# sr61-revC.net
KiCad netlist of a schematic drawn in EAGLE
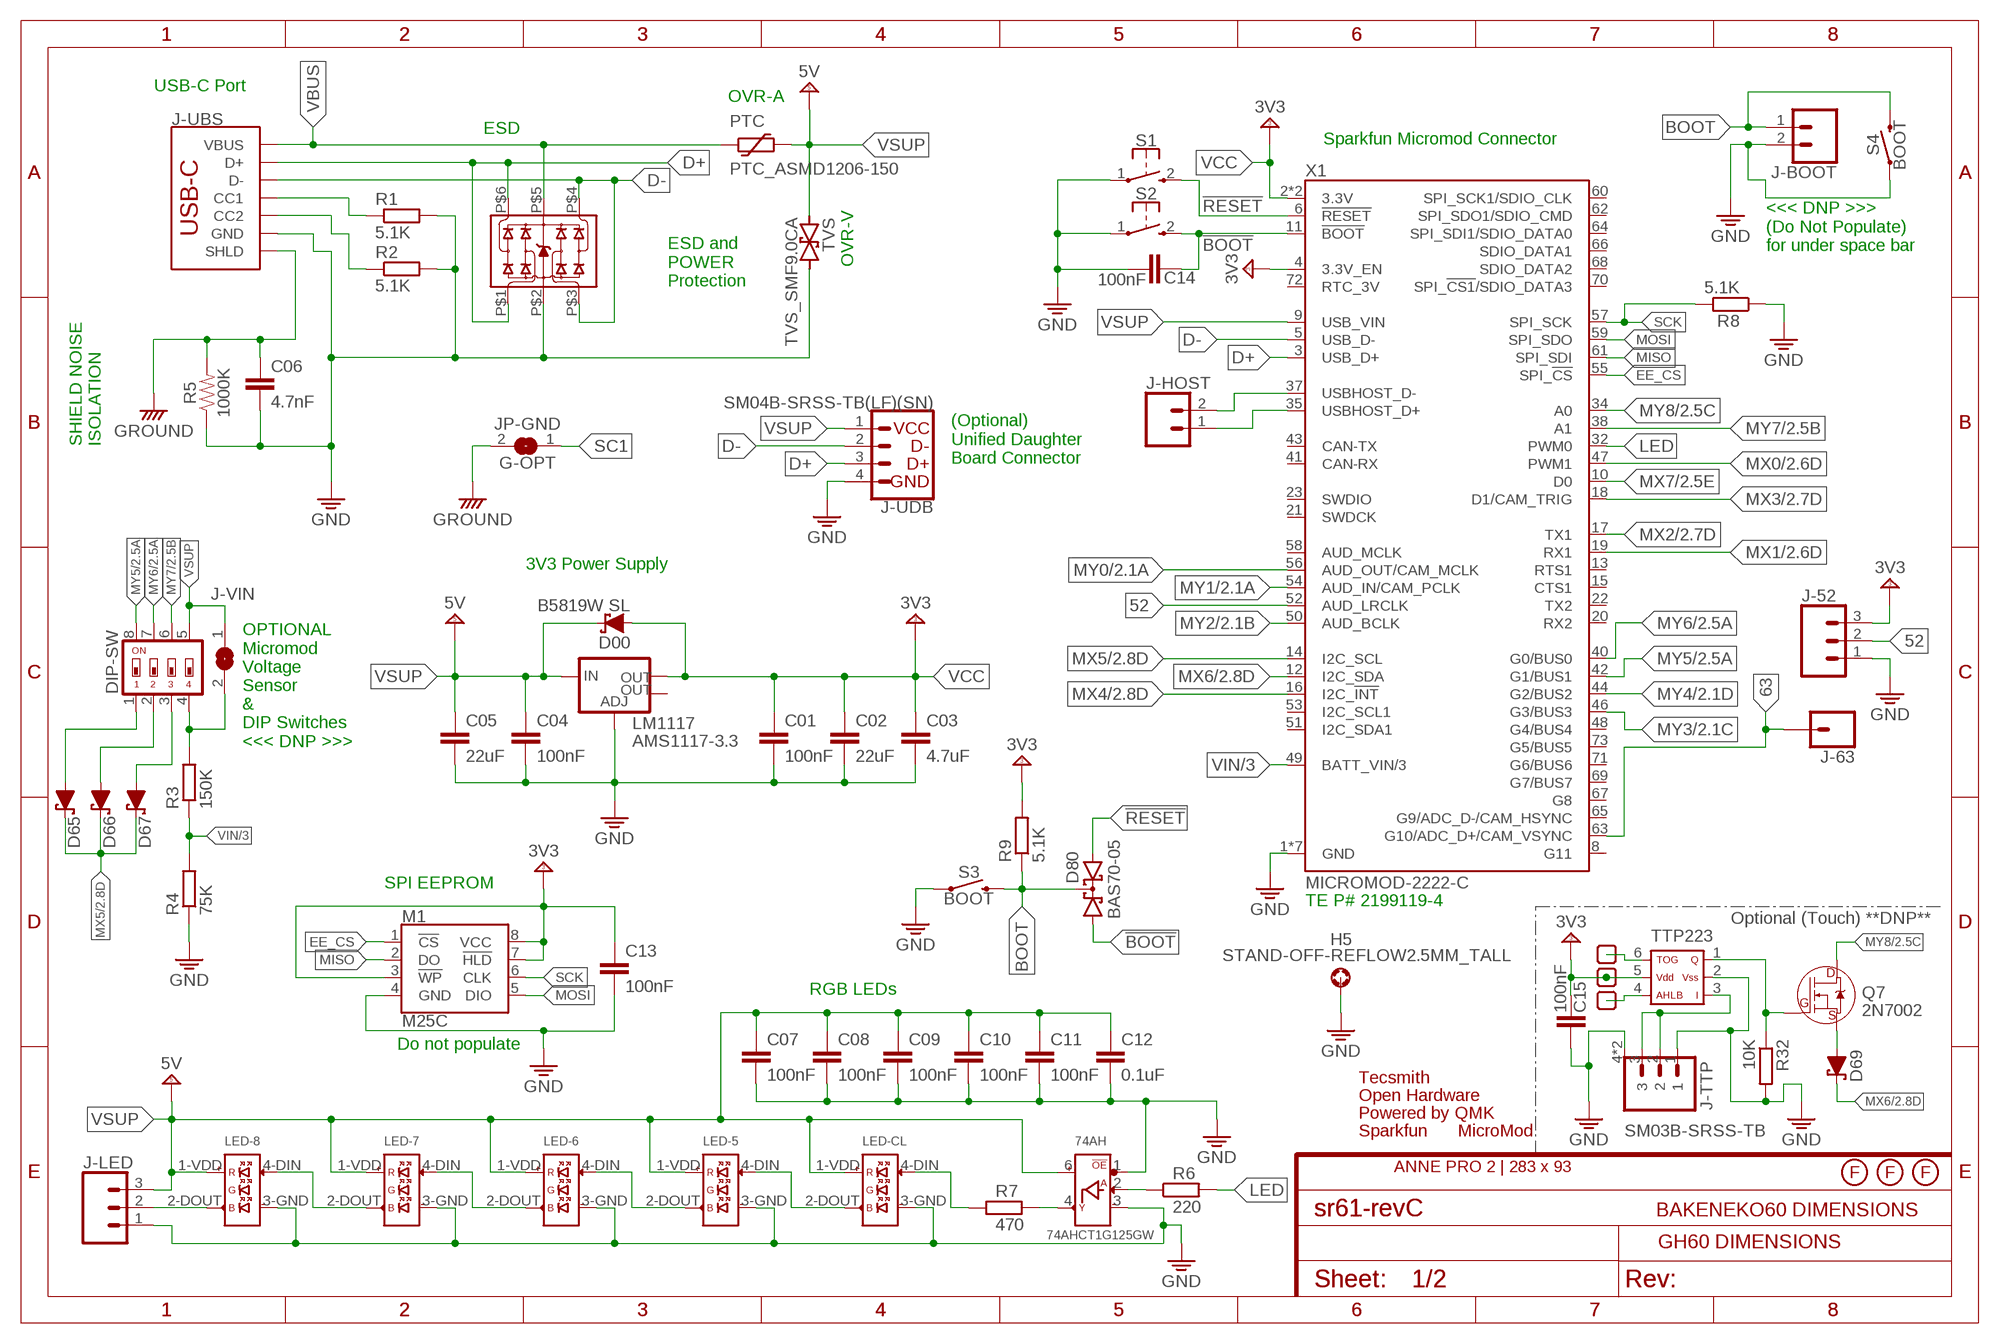
[diagram p0: schematic, sheet 1]
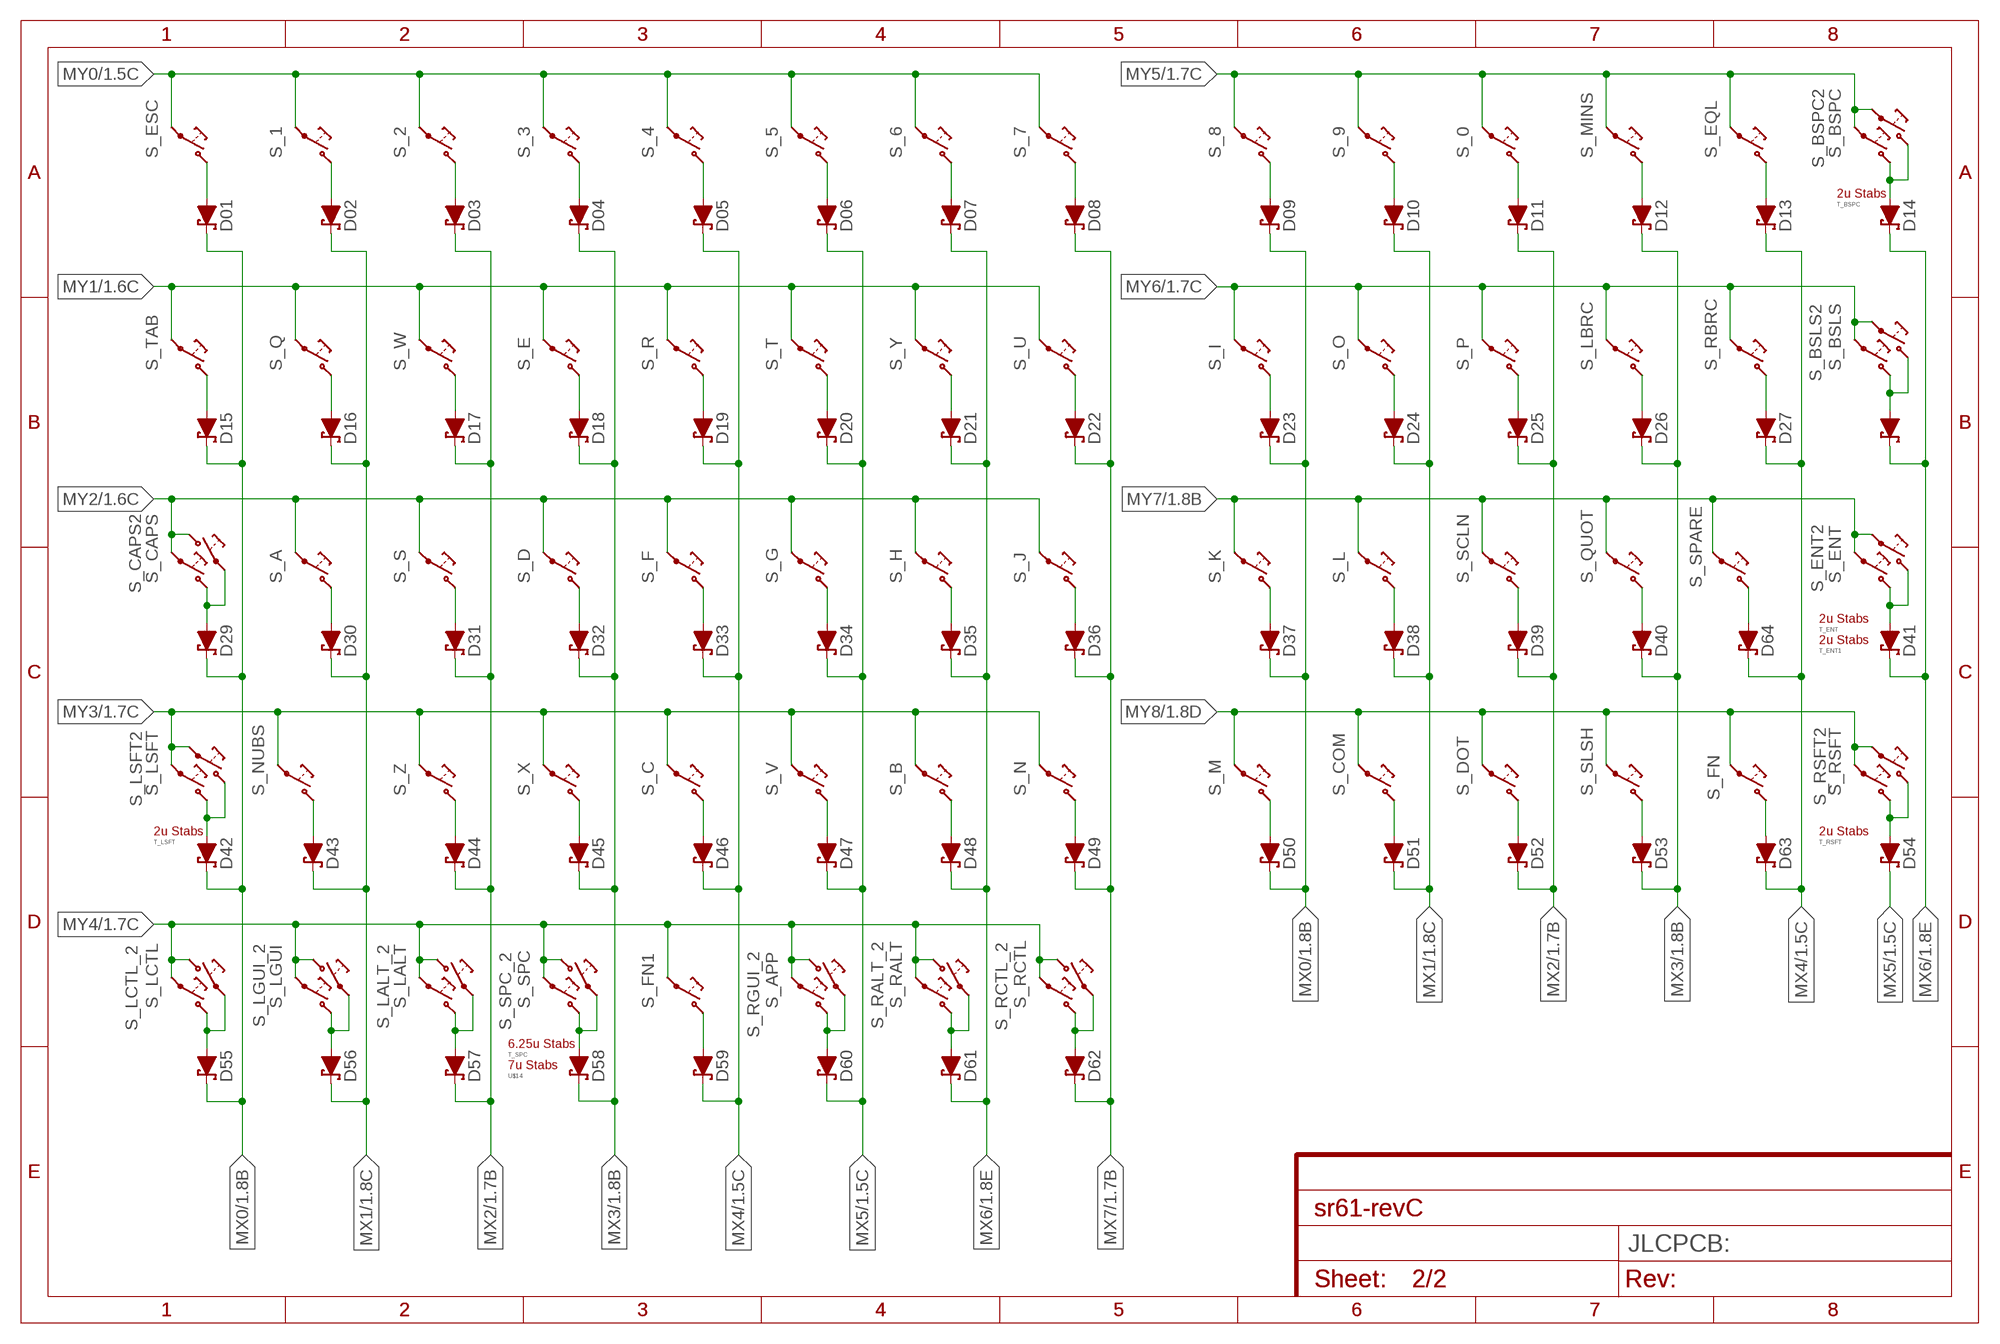
[diagram p1: schematic, sheet 2]

(export (version "E")
  (design (tool "Eeschema 10.0.6"))
  (components
    (comp (ref "D01")
      (value "1N5819WS")
      (footprint "eagle-import:SOD-123")
      (libsource (lib "eagle-import") (part "1N5819WS"))
    )
    (comp (ref "D02")
      (value "1N5819WS")
      (footprint "eagle-import:SOD-123")
      (libsource (lib "eagle-import") (part "1N5819WS"))
    )
    (comp (ref "D03")
      (value "1N5819WS")
      (footprint "eagle-import:SOD-123")
      (libsource (lib "eagle-import") (part "1N5819WS"))
    )
    (comp (ref "D04")
      (value "1N5819WS")
      (footprint "eagle-import:SOD-123")
      (libsource (lib "eagle-import") (part "1N5819WS"))
    )
    (comp (ref "D05")
      (value "1N5819WS")
      (footprint "eagle-import:SOD-123")
      (libsource (lib "eagle-import") (part "1N5819WS"))
    )
    (comp (ref "D06")
      (value "1N5819WS")
      (footprint "eagle-import:SOD-123")
      (libsource (lib "eagle-import") (part "1N5819WS"))
    )
    (comp (ref "D07")
      (value "1N5819WS")
      (footprint "eagle-import:SOD-123")
      (libsource (lib "eagle-import") (part "1N5819WS"))
    )
    (comp (ref "D08")
      (value "1N5819WS")
      (footprint "eagle-import:SOD-123")
      (libsource (lib "eagle-import") (part "1N5819WS"))
    )
    (comp (ref "D09")
      (value "1N5819WS")
      (footprint "eagle-import:SOD-123")
      (libsource (lib "eagle-import") (part "1N5819WS"))
    )
    (comp (ref "D10")
      (value "1N5819WS")
      (footprint "eagle-import:SOD-123")
      (libsource (lib "eagle-import") (part "1N5819WS"))
    )
    (comp (ref "D11")
      (value "1N5819WS")
      (footprint "eagle-import:SOD-123")
      (libsource (lib "eagle-import") (part "1N5819WS"))
    )
    (comp (ref "D12")
      (value "1N5819WS")
      (footprint "eagle-import:SOD-123")
      (libsource (lib "eagle-import") (part "1N5819WS"))
    )
    (comp (ref "D13")
      (value "1N5819WS")
      (footprint "eagle-import:SOD-123")
      (libsource (lib "eagle-import") (part "1N5819WS"))
    )
    (comp (ref "D14")
      (value "1N5819WS")
      (footprint "eagle-import:SOD-123")
      (libsource (lib "eagle-import") (part "1N5819WS"))
    )
    (comp (ref "D15")
      (value "1N5819WS")
      (footprint "eagle-import:SOD-123")
      (libsource (lib "eagle-import") (part "1N5819WS"))
    )
    (comp (ref "D16")
      (value "1N5819WS")
      (footprint "eagle-import:SOD-123")
      (libsource (lib "eagle-import") (part "1N5819WS"))
    )
    (comp (ref "D17")
      (value "1N5819WS")
      (footprint "eagle-import:SOD-123")
      (libsource (lib "eagle-import") (part "1N5819WS"))
    )
    (comp (ref "D18")
      (value "1N5819WS")
      (footprint "eagle-import:SOD-123")
      (libsource (lib "eagle-import") (part "1N5819WS"))
    )
    (comp (ref "D19")
      (value "1N5819WS")
      (footprint "eagle-import:SOD-123")
      (libsource (lib "eagle-import") (part "1N5819WS"))
    )
    (comp (ref "D20")
      (value "1N5819WS")
      (footprint "eagle-import:SOD-123")
      (libsource (lib "eagle-import") (part "1N5819WS"))
    )
    (comp (ref "D21")
      (value "1N5819WS")
      (footprint "eagle-import:SOD-123")
      (libsource (lib "eagle-import") (part "1N5819WS"))
    )
    (comp (ref "D22")
      (value "1N5819WS")
      (footprint "eagle-import:SOD-123")
      (libsource (lib "eagle-import") (part "1N5819WS"))
    )
    (comp (ref "D23")
      (value "1N5819WS")
      (footprint "eagle-import:SOD-123")
      (libsource (lib "eagle-import") (part "1N5819WS"))
    )
    (comp (ref "D24")
      (value "1N5819WS")
      (footprint "eagle-import:SOD-123")
      (libsource (lib "eagle-import") (part "1N5819WS"))
    )
    (comp (ref "D25")
      (value "1N5819WS")
      (footprint "eagle-import:SOD-123")
      (libsource (lib "eagle-import") (part "1N5819WS"))
    )
    (comp (ref "D26")
      (value "1N5819WS")
      (footprint "eagle-import:SOD-123")
      (libsource (lib "eagle-import") (part "1N5819WS"))
    )
    (comp (ref "D27")
      (value "1N5819WS")
      (footprint "eagle-import:SOD-123")
      (libsource (lib "eagle-import") (part "1N5819WS"))
    )
    (comp (ref "D28")
      (value "1N5819WS")
      (footprint "eagle-import:SOD-123")
      (libsource (lib "eagle-import") (part "1N5819WS"))
    )
    (comp (ref "D29")
      (value "1N5819WS")
      (footprint "eagle-import:SOD-123")
      (libsource (lib "eagle-import") (part "1N5819WS"))
    )
    (comp (ref "D30")
      (value "1N5819WS")
      (footprint "eagle-import:SOD-123")
      (libsource (lib "eagle-import") (part "1N5819WS"))
    )
    (comp (ref "D31")
      (value "1N5819WS")
      (footprint "eagle-import:SOD-123")
      (libsource (lib "eagle-import") (part "1N5819WS"))
    )
    (comp (ref "D32")
      (value "1N5819WS")
      (footprint "eagle-import:SOD-123")
      (libsource (lib "eagle-import") (part "1N5819WS"))
    )
    (comp (ref "D33")
      (value "1N5819WS")
      (footprint "eagle-import:SOD-123")
      (libsource (lib "eagle-import") (part "1N5819WS"))
    )
    (comp (ref "D34")
      (value "1N5819WS")
      (footprint "eagle-import:SOD-123")
      (libsource (lib "eagle-import") (part "1N5819WS"))
    )
    (comp (ref "D35")
      (value "1N5819WS")
      (footprint "eagle-import:SOD-123")
      (libsource (lib "eagle-import") (part "1N5819WS"))
    )
    (comp (ref "D36")
      (value "1N5819WS")
      (footprint "eagle-import:SOD-123")
      (libsource (lib "eagle-import") (part "1N5819WS"))
    )
    (comp (ref "D37")
      (value "1N5819WS")
      (footprint "eagle-import:SOD-123")
      (libsource (lib "eagle-import") (part "1N5819WS"))
    )
    (comp (ref "D38")
      (value "1N5819WS")
      (footprint "eagle-import:SOD-123")
      (libsource (lib "eagle-import") (part "1N5819WS"))
    )
    (comp (ref "D39")
      (value "1N5819WS")
      (footprint "eagle-import:SOD-123")
      (libsource (lib "eagle-import") (part "1N5819WS"))
    )
    (comp (ref "D40")
      (value "1N5819WS")
      (footprint "eagle-import:SOD-123")
      (libsource (lib "eagle-import") (part "1N5819WS"))
    )
    (comp (ref "D41")
      (value "1N5819WS")
      (footprint "eagle-import:SOD-123")
      (libsource (lib "eagle-import") (part "1N5819WS"))
    )
    (comp (ref "D42")
      (value "1N5819WS")
      (footprint "eagle-import:SOD-123")
      (libsource (lib "eagle-import") (part "1N5819WS"))
    )
    (comp (ref "D43")
      (value "1N5819WS")
      (footprint "eagle-import:SOD-123")
      (libsource (lib "eagle-import") (part "1N5819WS"))
    )
    (comp (ref "D44")
      (value "1N5819WS")
      (footprint "eagle-import:SOD-123")
      (libsource (lib "eagle-import") (part "1N5819WS"))
    )
    (comp (ref "D45")
      (value "1N5819WS")
      (footprint "eagle-import:SOD-123")
      (libsource (lib "eagle-import") (part "1N5819WS"))
    )
    (comp (ref "D46")
      (value "1N5819WS")
      (footprint "eagle-import:SOD-123")
      (libsource (lib "eagle-import") (part "1N5819WS"))
    )
    (comp (ref "D47")
      (value "1N5819WS")
      (footprint "eagle-import:SOD-123")
      (libsource (lib "eagle-import") (part "1N5819WS"))
    )
    (comp (ref "D48")
      (value "1N5819WS")
      (footprint "eagle-import:SOD-123")
      (libsource (lib "eagle-import") (part "1N5819WS"))
    )
    (comp (ref "D49")
      (value "1N5819WS")
      (footprint "eagle-import:SOD-123")
      (libsource (lib "eagle-import") (part "1N5819WS"))
    )
    (comp (ref "D50")
      (value "1N5819WS")
      (footprint "eagle-import:SOD-123")
      (libsource (lib "eagle-import") (part "1N5819WS"))
    )
    (comp (ref "D51")
      (value "1N5819WS")
      (footprint "eagle-import:SOD-123")
      (libsource (lib "eagle-import") (part "1N5819WS"))
    )
    (comp (ref "D52")
      (value "1N5819WS")
      (footprint "eagle-import:SOD-123")
      (libsource (lib "eagle-import") (part "1N5819WS"))
    )
    (comp (ref "D53")
      (value "1N5819WS")
      (footprint "eagle-import:SOD-123")
      (libsource (lib "eagle-import") (part "1N5819WS"))
    )
    (comp (ref "D54")
      (value "1N5819WS")
      (footprint "eagle-import:SOD-123")
      (libsource (lib "eagle-import") (part "1N5819WS"))
    )
    (comp (ref "D55")
      (value "1N5819WS")
      (footprint "eagle-import:SOD-123")
      (libsource (lib "eagle-import") (part "1N5819WS"))
    )
    (comp (ref "D56")
      (value "1N5819WS")
      (footprint "eagle-import:SOD-123")
      (libsource (lib "eagle-import") (part "1N5819WS"))
    )
    (comp (ref "D57")
      (value "1N5819WS")
      (footprint "eagle-import:SOD-123")
      (libsource (lib "eagle-import") (part "1N5819WS"))
    )
    (comp (ref "D58")
      (value "1N5819WS")
      (footprint "eagle-import:SOD-123")
      (libsource (lib "eagle-import") (part "1N5819WS"))
    )
    (comp (ref "D59")
      (value "1N5819WS")
      (footprint "eagle-import:SOD-123")
      (libsource (lib "eagle-import") (part "1N5819WS"))
    )
    (comp (ref "D60")
      (value "1N5819WS")
      (footprint "eagle-import:SOD-123")
      (libsource (lib "eagle-import") (part "1N5819WS"))
    )
    (comp (ref "D61")
      (value "1N5819WS")
      (footprint "eagle-import:SOD-123")
      (libsource (lib "eagle-import") (part "1N5819WS"))
    )
    (comp (ref "D62")
      (value "1N5819WS")
      (footprint "eagle-import:SOD-123")
      (libsource (lib "eagle-import") (part "1N5819WS"))
    )
    (comp (ref "D63")
      (value "1N5819WS")
      (footprint "eagle-import:SOD-123")
      (libsource (lib "eagle-import") (part "1N5819WS"))
    )
    (comp (ref "D64")
      (value "1N5819WS")
      (footprint "eagle-import:SOD-123")
      (libsource (lib "eagle-import") (part "1N5819WS"))
    )
    (comp (ref "S_0")
      (value "MX-5-PIN-HOTSWAP-VIA")
      (footprint "eagle-import:MX-5-PIN-HOTSWAP-VIA")
      (libsource (lib "eagle-import") (part "MX-5-PIN-HOTSWAP-VIA"))
    )
    (comp (ref "S_1")
      (value "MX-5-PIN-HOTSWAP-VIA")
      (footprint "eagle-import:MX-5-PIN-HOTSWAP-VIA")
      (libsource (lib "eagle-import") (part "MX-5-PIN-HOTSWAP-VIA"))
    )
    (comp (ref "S_2")
      (value "MX-5-PIN-HOTSWAP-VIA")
      (footprint "eagle-import:MX-5-PIN-HOTSWAP-VIA")
      (libsource (lib "eagle-import") (part "MX-5-PIN-HOTSWAP-VIA"))
    )
    (comp (ref "S_3")
      (value "MX-5-PIN-HOTSWAP-VIA")
      (footprint "eagle-import:MX-5-PIN-HOTSWAP-VIA")
      (libsource (lib "eagle-import") (part "MX-5-PIN-HOTSWAP-VIA"))
    )
    (comp (ref "S_4")
      (value "MX-5-PIN-HOTSWAP-VIA")
      (footprint "eagle-import:MX-5-PIN-HOTSWAP-VIA")
      (libsource (lib "eagle-import") (part "MX-5-PIN-HOTSWAP-VIA"))
    )
    (comp (ref "S_5")
      (value "MX-5-PIN-HOTSWAP-VIA")
      (footprint "eagle-import:MX-5-PIN-HOTSWAP-VIA")
      (libsource (lib "eagle-import") (part "MX-5-PIN-HOTSWAP-VIA"))
    )
    (comp (ref "S_6")
      (value "MX-5-PIN-HOTSWAP-VIA")
      (footprint "eagle-import:MX-5-PIN-HOTSWAP-VIA")
      (libsource (lib "eagle-import") (part "MX-5-PIN-HOTSWAP-VIA"))
    )
    (comp (ref "S_7")
      (value "MX-5-PIN-HOTSWAP-VIA")
      (footprint "eagle-import:MX-5-PIN-HOTSWAP-VIA")
      (libsource (lib "eagle-import") (part "MX-5-PIN-HOTSWAP-VIA"))
    )
    (comp (ref "S_8")
      (value "MX-5-PIN-HOTSWAP-VIA")
      (footprint "eagle-import:MX-5-PIN-HOTSWAP-VIA")
      (libsource (lib "eagle-import") (part "MX-5-PIN-HOTSWAP-VIA"))
    )
    (comp (ref "S_9")
      (value "MX-5-PIN-HOTSWAP-VIA")
      (footprint "eagle-import:MX-5-PIN-HOTSWAP-VIA")
      (libsource (lib "eagle-import") (part "MX-5-PIN-HOTSWAP-VIA"))
    )
    (comp (ref "S_A")
      (value "MX-5-PIN-HOTSWAP-VIA")
      (footprint "eagle-import:MX-5-PIN-HOTSWAP-VIA")
      (libsource (lib "eagle-import") (part "MX-5-PIN-HOTSWAP-VIA"))
    )
    (comp (ref "S_APP")
      (value "MX-5-PIN-HOTSWAP-VIA")
      (footprint "eagle-import:MX-5-PIN-HOTSWAP-VIA")
      (libsource (lib "eagle-import") (part "MX-5-PIN-HOTSWAP-VIA"))
    )
    (comp (ref "S_B")
      (value "MX-5-PIN-HOTSWAP-VIA")
      (footprint "eagle-import:MX-5-PIN-HOTSWAP-VIA")
      (libsource (lib "eagle-import") (part "MX-5-PIN-HOTSWAP-VIA"))
    )
    (comp (ref "S_BSLS")
      (value "MX-5-PIN-HOTSWAP-VIA")
      (footprint "eagle-import:MX-5-PIN-HOTSWAP-VIA")
      (libsource (lib "eagle-import") (part "MX-5-PIN-HOTSWAP-VIA"))
    )
    (comp (ref "S_BSLS2")
      (value "MX-5-PIN-HOTSWAP-VIANO-SILK")
      (footprint "eagle-import:MX-5-PIN-HOTSWAP-VIA-NS")
      (libsource (lib "eagle-import") (part "MX-5-PIN-HOTSWAP-VIANO-SILK"))
    )
    (comp (ref "S_BSPC")
      (value "MX-5-PIN-HOTSWAP-VIA")
      (footprint "eagle-import:MX-5-PIN-HOTSWAP-VIA")
      (libsource (lib "eagle-import") (part "MX-5-PIN-HOTSWAP-VIA"))
    )
    (comp (ref "S_BSPC2")
      (value "MX-5-PIN-HOTSWAP-VIANO-SILK")
      (footprint "eagle-import:MX-5-PIN-HOTSWAP-VIA-NS")
      (libsource (lib "eagle-import") (part "MX-5-PIN-HOTSWAP-VIANO-SILK"))
    )
    (comp (ref "S_C")
      (value "MX-5-PIN-HOTSWAP-VIA")
      (footprint "eagle-import:MX-5-PIN-HOTSWAP-VIA")
      (libsource (lib "eagle-import") (part "MX-5-PIN-HOTSWAP-VIA"))
    )
    (comp (ref "S_CAPS")
      (value "MX-5-PIN-HOTSWAP-VIA")
      (footprint "eagle-import:MX-5-PIN-HOTSWAP-VIA")
      (libsource (lib "eagle-import") (part "MX-5-PIN-HOTSWAP-VIA"))
    )
    (comp (ref "S_CAPS2")
      (value "MX-5-PIN-MILMAX-3305-XNO-SILK")
      (footprint "eagle-import:MX-5-PIN-MILMAX-3305-X-NS")
      (libsource (lib "eagle-import") (part "MX-5-PIN-MILMAX-3305-XNO-SILK"))
    )
    (comp (ref "S_COM")
      (value "MX-5-PIN-HOTSWAP-VIA")
      (footprint "eagle-import:MX-5-PIN-HOTSWAP-VIA")
      (libsource (lib "eagle-import") (part "MX-5-PIN-HOTSWAP-VIA"))
    )
    (comp (ref "S_D")
      (value "MX-5-PIN-HOTSWAP-VIA")
      (footprint "eagle-import:MX-5-PIN-HOTSWAP-VIA")
      (libsource (lib "eagle-import") (part "MX-5-PIN-HOTSWAP-VIA"))
    )
    (comp (ref "S_DOT")
      (value "MX-5-PIN-HOTSWAP-VIA")
      (footprint "eagle-import:MX-5-PIN-HOTSWAP-VIA")
      (libsource (lib "eagle-import") (part "MX-5-PIN-HOTSWAP-VIA"))
    )
    (comp (ref "S_E")
      (value "MX-5-PIN-HOTSWAP-VIA")
      (footprint "eagle-import:MX-5-PIN-HOTSWAP-VIA")
      (libsource (lib "eagle-import") (part "MX-5-PIN-HOTSWAP-VIA"))
    )
    (comp (ref "S_ENT")
      (value "MX-5-PIN-HOTSWAP-VIA")
      (footprint "eagle-import:MX-5-PIN-HOTSWAP-VIA")
      (libsource (lib "eagle-import") (part "MX-5-PIN-HOTSWAP-VIA"))
    )
    (comp (ref "S_ENT2")
      (value "MX-5-PIN-HOTSWAP-VIANO-SILK")
      (footprint "eagle-import:MX-5-PIN-HOTSWAP-VIA-NS")
      (libsource (lib "eagle-import") (part "MX-5-PIN-HOTSWAP-VIANO-SILK"))
    )
    (comp (ref "S_EQL")
      (value "MX-5-PIN-HOTSWAP-VIA")
      (footprint "eagle-import:MX-5-PIN-HOTSWAP-VIA")
      (libsource (lib "eagle-import") (part "MX-5-PIN-HOTSWAP-VIA"))
    )
    (comp (ref "S_ESC")
      (value "MX-5-PIN-HOTSWAP-VIA")
      (footprint "eagle-import:MX-5-PIN-HOTSWAP-VIA")
      (libsource (lib "eagle-import") (part "MX-5-PIN-HOTSWAP-VIA"))
    )
    (comp (ref "S_F")
      (value "MX-5-PIN-HOTSWAP-VIA")
      (footprint "eagle-import:MX-5-PIN-HOTSWAP-VIA")
      (libsource (lib "eagle-import") (part "MX-5-PIN-HOTSWAP-VIA"))
    )
    (comp (ref "S_FN")
      (value "MX-5-PIN-HOTSWAP-VIANO-SILK")
      (footprint "eagle-import:MX-5-PIN-HOTSWAP-VIA-NS")
      (libsource (lib "eagle-import") (part "MX-5-PIN-HOTSWAP-VIANO-SILK"))
    )
    (comp (ref "S_FN1")
      (value "MX-5-PIN-HOTSWAP-VIA")
      (footprint "eagle-import:MX-5-PIN-HOTSWAP-VIA")
      (libsource (lib "eagle-import") (part "MX-5-PIN-HOTSWAP-VIA"))
    )
    (comp (ref "S_G")
      (value "MX-5-PIN-HOTSWAP-VIA")
      (footprint "eagle-import:MX-5-PIN-HOTSWAP-VIA")
      (libsource (lib "eagle-import") (part "MX-5-PIN-HOTSWAP-VIA"))
    )
    (comp (ref "S_H")
      (value "MX-5-PIN-HOTSWAP-VIA")
      (footprint "eagle-import:MX-5-PIN-HOTSWAP-VIA")
      (libsource (lib "eagle-import") (part "MX-5-PIN-HOTSWAP-VIA"))
    )
    (comp (ref "S_I")
      (value "MX-5-PIN-HOTSWAP-VIA")
      (footprint "eagle-import:MX-5-PIN-HOTSWAP-VIA")
      (libsource (lib "eagle-import") (part "MX-5-PIN-HOTSWAP-VIA"))
    )
    (comp (ref "S_J")
      (value "MX-5-PIN-HOTSWAP-VIA")
      (footprint "eagle-import:MX-5-PIN-HOTSWAP-VIA")
      (libsource (lib "eagle-import") (part "MX-5-PIN-HOTSWAP-VIA"))
    )
    (comp (ref "S_K")
      (value "MX-5-PIN-HOTSWAP-VIA")
      (footprint "eagle-import:MX-5-PIN-HOTSWAP-VIA")
      (libsource (lib "eagle-import") (part "MX-5-PIN-HOTSWAP-VIA"))
    )
    (comp (ref "S_L")
      (value "MX-5-PIN-HOTSWAP-VIA")
      (footprint "eagle-import:MX-5-PIN-HOTSWAP-VIA")
      (libsource (lib "eagle-import") (part "MX-5-PIN-HOTSWAP-VIA"))
    )
    (comp (ref "S_LALT")
      (value "MX-5-PIN-HOTSWAP-VIA")
      (footprint "eagle-import:MX-5-PIN-HOTSWAP-VIA")
      (libsource (lib "eagle-import") (part "MX-5-PIN-HOTSWAP-VIA"))
    )
    (comp (ref "S_LALT_2")
      (value "MX-5-PIN-HOTSWAP-VIANO-SILK")
      (footprint "eagle-import:MX-5-PIN-HOTSWAP-VIA-NS")
      (libsource (lib "eagle-import") (part "MX-5-PIN-HOTSWAP-VIANO-SILK"))
    )
    (comp (ref "S_LBRC")
      (value "MX-5-PIN-HOTSWAP-VIA")
      (footprint "eagle-import:MX-5-PIN-HOTSWAP-VIA")
      (libsource (lib "eagle-import") (part "MX-5-PIN-HOTSWAP-VIA"))
    )
    (comp (ref "S_LCTL")
      (value "MX-5-PIN-HOTSWAP-VIA")
      (footprint "eagle-import:MX-5-PIN-HOTSWAP-VIA")
      (libsource (lib "eagle-import") (part "MX-5-PIN-HOTSWAP-VIA"))
    )
    (comp (ref "S_LCTL_2")
      (value "MX-5-PIN-HOTSWAP-VIANO-SILK")
      (footprint "eagle-import:MX-5-PIN-HOTSWAP-VIA-NS")
      (libsource (lib "eagle-import") (part "MX-5-PIN-HOTSWAP-VIANO-SILK"))
    )
    (comp (ref "S_LGUI")
      (value "MX-5-PIN-HOTSWAP-VIA")
      (footprint "eagle-import:MX-5-PIN-HOTSWAP-VIA")
      (libsource (lib "eagle-import") (part "MX-5-PIN-HOTSWAP-VIA"))
    )
    (comp (ref "S_LGUI_2")
      (value "MX-5-PIN-HOTSWAP-VIANO-SILK")
      (footprint "eagle-import:MX-5-PIN-HOTSWAP-VIA-NS")
      (libsource (lib "eagle-import") (part "MX-5-PIN-HOTSWAP-VIANO-SILK"))
    )
    (comp (ref "S_LSFT")
      (value "MX-5-PIN-HOTSWAP-VIA")
      (footprint "eagle-import:MX-5-PIN-HOTSWAP-VIA")
      (libsource (lib "eagle-import") (part "MX-5-PIN-HOTSWAP-VIA"))
    )
    (comp (ref "S_LSFT2")
      (value "MX-5-PIN-HOTSWAP-VIANO-SILK")
      (footprint "eagle-import:MX-5-PIN-HOTSWAP-VIA-NS")
      (libsource (lib "eagle-import") (part "MX-5-PIN-HOTSWAP-VIANO-SILK"))
    )
    (comp (ref "S_M")
      (value "MX-5-PIN-HOTSWAP-VIA")
      (footprint "eagle-import:MX-5-PIN-HOTSWAP-VIA")
      (libsource (lib "eagle-import") (part "MX-5-PIN-HOTSWAP-VIA"))
    )
    (comp (ref "S_MINS")
      (value "MX-5-PIN-HOTSWAP-VIA")
      (footprint "eagle-import:MX-5-PIN-HOTSWAP-VIA")
      (libsource (lib "eagle-import") (part "MX-5-PIN-HOTSWAP-VIA"))
    )
    (comp (ref "S_N")
      (value "MX-5-PIN-HOTSWAP-VIA")
      (footprint "eagle-import:MX-5-PIN-HOTSWAP-VIA")
      (libsource (lib "eagle-import") (part "MX-5-PIN-HOTSWAP-VIA"))
    )
    (comp (ref "S_NUBS")
      (value "MX-5-PIN-HOTSWAP-VIANO-SILK")
      (footprint "eagle-import:MX-5-PIN-HOTSWAP-VIA-NS")
      (libsource (lib "eagle-import") (part "MX-5-PIN-HOTSWAP-VIANO-SILK"))
    )
    (comp (ref "S_O")
      (value "MX-5-PIN-HOTSWAP-VIA")
      (footprint "eagle-import:MX-5-PIN-HOTSWAP-VIA")
      (libsource (lib "eagle-import") (part "MX-5-PIN-HOTSWAP-VIA"))
    )
    (comp (ref "S_P")
      (value "MX-5-PIN-HOTSWAP-VIA")
      (footprint "eagle-import:MX-5-PIN-HOTSWAP-VIA")
      (libsource (lib "eagle-import") (part "MX-5-PIN-HOTSWAP-VIA"))
    )
    (comp (ref "S_Q")
      (value "MX-5-PIN-HOTSWAP-VIA")
      (footprint "eagle-import:MX-5-PIN-HOTSWAP-VIA")
      (libsource (lib "eagle-import") (part "MX-5-PIN-HOTSWAP-VIA"))
    )
    (comp (ref "S_QUOT")
      (value "MX-5-PIN-HOTSWAP-VIA")
      (footprint "eagle-import:MX-5-PIN-HOTSWAP-VIA")
      (libsource (lib "eagle-import") (part "MX-5-PIN-HOTSWAP-VIA"))
    )
    (comp (ref "S_R")
      (value "MX-5-PIN-HOTSWAP-VIA")
      (footprint "eagle-import:MX-5-PIN-HOTSWAP-VIA")
      (libsource (lib "eagle-import") (part "MX-5-PIN-HOTSWAP-VIA"))
    )
    (comp (ref "S_RALT")
      (value "MX-5-PIN-HOTSWAP-VIA")
      (footprint "eagle-import:MX-5-PIN-HOTSWAP-VIA")
      (libsource (lib "eagle-import") (part "MX-5-PIN-HOTSWAP-VIA"))
    )
    (comp (ref "S_RALT_2")
      (value "MX-5-PIN-HOTSWAP-VIANO-SILK")
      (footprint "eagle-import:MX-5-PIN-HOTSWAP-VIA-NS")
      (libsource (lib "eagle-import") (part "MX-5-PIN-HOTSWAP-VIANO-SILK"))
    )
    (comp (ref "S_RBRC")
      (value "MX-5-PIN-HOTSWAP-VIA")
      (footprint "eagle-import:MX-5-PIN-HOTSWAP-VIA")
      (libsource (lib "eagle-import") (part "MX-5-PIN-HOTSWAP-VIA"))
    )
    (comp (ref "S_RCTL")
      (value "MX-5-PIN-HOTSWAP-VIA")
      (footprint "eagle-import:MX-5-PIN-HOTSWAP-VIA")
      (libsource (lib "eagle-import") (part "MX-5-PIN-HOTSWAP-VIA"))
    )
    (comp (ref "S_RCTL_2")
      (value "MX-5-PIN-HOTSWAP-VIANO-SILK")
      (footprint "eagle-import:MX-5-PIN-HOTSWAP-VIA-NS")
      (libsource (lib "eagle-import") (part "MX-5-PIN-HOTSWAP-VIANO-SILK"))
    )
    (comp (ref "S_RGUI_2")
      (value "MX-5-PIN-HOTSWAP-VIANO-SILK")
      (footprint "eagle-import:MX-5-PIN-HOTSWAP-VIA-NS")
      (libsource (lib "eagle-import") (part "MX-5-PIN-HOTSWAP-VIANO-SILK"))
    )
    (comp (ref "S_RSFT")
      (value "MX-5-PIN-HOTSWAP-VIA")
      (footprint "eagle-import:MX-5-PIN-HOTSWAP-VIA")
      (libsource (lib "eagle-import") (part "MX-5-PIN-HOTSWAP-VIA"))
    )
    (comp (ref "S_RSFT2")
      (value "MX-5-PIN-HOTSWAP-VIANO-SILK")
      (footprint "eagle-import:MX-5-PIN-HOTSWAP-VIA-NS")
      (libsource (lib "eagle-import") (part "MX-5-PIN-HOTSWAP-VIANO-SILK"))
    )
    (comp (ref "S_S")
      (value "MX-5-PIN-HOTSWAP-VIA")
      (footprint "eagle-import:MX-5-PIN-HOTSWAP-VIA")
      (libsource (lib "eagle-import") (part "MX-5-PIN-HOTSWAP-VIA"))
    )
    (comp (ref "S_SCLN")
      (value "MX-5-PIN-HOTSWAP-VIA")
      (footprint "eagle-import:MX-5-PIN-HOTSWAP-VIA")
      (libsource (lib "eagle-import") (part "MX-5-PIN-HOTSWAP-VIA"))
    )
    (comp (ref "S_SLSH")
      (value "MX-5-PIN-HOTSWAP-VIA")
      (footprint "eagle-import:MX-5-PIN-HOTSWAP-VIA")
      (libsource (lib "eagle-import") (part "MX-5-PIN-HOTSWAP-VIA"))
    )
    (comp (ref "S_SPARE")
      (value "MX-5-PIN-HOTSWAP-VIANO-SILK")
      (footprint "eagle-import:MX-5-PIN-HOTSWAP-VIA-NS")
      (libsource (lib "eagle-import") (part "MX-5-PIN-HOTSWAP-VIANO-SILK"))
    )
    (comp (ref "S_SPC")
      (value "MX-5-PIN-HOTSWAP-VIA")
      (footprint "eagle-import:MX-5-PIN-HOTSWAP-VIA")
      (libsource (lib "eagle-import") (part "MX-5-PIN-HOTSWAP-VIA"))
    )
    (comp (ref "S_SPC_2")
      (value "MX-5-PIN-HOTSWAP-VIANO-SILK")
      (footprint "eagle-import:MX-5-PIN-HOTSWAP-VIA-NS")
      (libsource (lib "eagle-import") (part "MX-5-PIN-HOTSWAP-VIANO-SILK"))
    )
    (comp (ref "S_T")
      (value "MX-5-PIN-HOTSWAP-VIA")
      (footprint "eagle-import:MX-5-PIN-HOTSWAP-VIA")
      (libsource (lib "eagle-import") (part "MX-5-PIN-HOTSWAP-VIA"))
    )
    (comp (ref "S_TAB")
      (value "MX-5-PIN-HOTSWAP-VIA")
      (footprint "eagle-import:MX-5-PIN-HOTSWAP-VIA")
      (libsource (lib "eagle-import") (part "MX-5-PIN-HOTSWAP-VIA"))
    )
    (comp (ref "S_U")
      (value "MX-5-PIN-HOTSWAP-VIA")
      (footprint "eagle-import:MX-5-PIN-HOTSWAP-VIA")
      (libsource (lib "eagle-import") (part "MX-5-PIN-HOTSWAP-VIA"))
    )
    (comp (ref "S_V")
      (value "MX-5-PIN-HOTSWAP-VIA")
      (footprint "eagle-import:MX-5-PIN-HOTSWAP-VIA")
      (libsource (lib "eagle-import") (part "MX-5-PIN-HOTSWAP-VIA"))
    )
    (comp (ref "S_W")
      (value "MX-5-PIN-HOTSWAP-VIA")
      (footprint "eagle-import:MX-5-PIN-HOTSWAP-VIA")
      (libsource (lib "eagle-import") (part "MX-5-PIN-HOTSWAP-VIA"))
    )
    (comp (ref "S_X")
      (value "MX-5-PIN-HOTSWAP-VIA")
      (footprint "eagle-import:MX-5-PIN-HOTSWAP-VIA")
      (libsource (lib "eagle-import") (part "MX-5-PIN-HOTSWAP-VIA"))
    )
    (comp (ref "S_Y")
      (value "MX-5-PIN-HOTSWAP-VIA")
      (footprint "eagle-import:MX-5-PIN-HOTSWAP-VIA")
      (libsource (lib "eagle-import") (part "MX-5-PIN-HOTSWAP-VIA"))
    )
    (comp (ref "S_Z")
      (value "MX-5-PIN-HOTSWAP-VIA")
      (footprint "eagle-import:MX-5-PIN-HOTSWAP-VIA")
      (libsource (lib "eagle-import") (part "MX-5-PIN-HOTSWAP-VIA"))
    )
    (comp (ref "T_BSPC")
      (value "MX-STABS-200U")
      (footprint "eagle-import:MX-STABS-200U")
      (libsource (lib "eagle-import") (part "MX-STABS-200U"))
    )
    (comp (ref "T_ENT")
      (value "MX-STABS-200U")
      (footprint "eagle-import:MX-STABS-200U")
      (libsource (lib "eagle-import") (part "MX-STABS-200U"))
    )
    (comp (ref "T_ENT1")
      (value "MX-STABS-200U")
      (footprint "eagle-import:MX-STABS-200U")
      (libsource (lib "eagle-import") (part "MX-STABS-200U"))
    )
    (comp (ref "T_LSFT")
      (value "MX-STABS-200U")
      (footprint "eagle-import:MX-STABS-200U")
      (libsource (lib "eagle-import") (part "MX-STABS-200U"))
    )
    (comp (ref "T_RSFT")
      (value "MX-STABS-200U")
      (footprint "eagle-import:MX-STABS-200U")
      (libsource (lib "eagle-import") (part "MX-STABS-200U"))
    )
    (comp (ref "T_SPC")
      (value "MX-STABS-625U")
      (footprint "eagle-import:MX-STABS-625U")
      (libsource (lib "eagle-import") (part "MX-STABS-625U"))
    )
    (comp (ref "U$14")
      (value "MX-STABS-700U")
      (footprint "eagle-import:MX-STABS-700U")
      (libsource (lib "eagle-import") (part "MX-STABS-700U"))
    )
    (comp (ref "U$26")
      (value "?")
      (footprint "eagle-import:JLC_ORDER_NUMBER_QR_5X5")
      (libsource (lib "eagle-import") (part "JLC_ORDER_NUMBER_QRQR_5X5"))
    )
    (comp (ref "74AH")
      (value "74AHCT1G125GW")
      (footprint "eagle-import:SC-88A__TSSOP5__SOT353-1")
      (libsource (lib "eagle-import") (part "74AHCT1G125GW"))
    )
    (comp (ref "C01")
      (value "100nF")
      (footprint "eagle-import:0603")
      (libsource (lib "eagle-import") (part "0.1UF-0603-25V-5%"))
    )
    (comp (ref "C02")
      (value "22uF")
      (footprint "eagle-import:0603")
      (libsource (lib "eagle-import") (part "0.22UF-0603-25V-10%"))
    )
    (comp (ref "C03")
      (value "4.7uF")
      (footprint "eagle-import:0603")
      (libsource (lib "eagle-import") (part "1.0NF/1000PF-0603-50V-10%"))
    )
    (comp (ref "C04")
      (value "100nF")
      (footprint "eagle-import:0603")
      (libsource (lib "eagle-import") (part "0.1UF-0603-25V-5%"))
    )
    (comp (ref "C05")
      (value "22uF")
      (footprint "eagle-import:0603")
      (libsource (lib "eagle-import") (part "0.22UF-0603-25V-10%"))
    )
    (comp (ref "C06")
      (value "4.7nF")
      (footprint "eagle-import:0603")
      (libsource (lib "eagle-import") (part "0.1UF-0603-25V-5%"))
    )
    (comp (ref "C07")
      (value "100nF")
      (footprint "eagle-import:C0603")
      (libsource (lib "eagle-import") (part "C-EUC0603"))
    )
    (comp (ref "C08")
      (value "100nF")
      (footprint "eagle-import:C0603")
      (libsource (lib "eagle-import") (part "C-EUC0603"))
    )
    (comp (ref "C09")
      (value "100nF")
      (footprint "eagle-import:C0603")
      (libsource (lib "eagle-import") (part "C-EUC0603"))
    )
    (comp (ref "C10")
      (value "100nF")
      (footprint "eagle-import:C0603")
      (libsource (lib "eagle-import") (part "C-EUC0603"))
    )
    (comp (ref "C11")
      (value "100nF")
      (footprint "eagle-import:C0603")
      (libsource (lib "eagle-import") (part "C-EUC0603"))
    )
    (comp (ref "C12")
      (value "0.1uF")
      (footprint "eagle-import:C0603")
      (libsource (lib "eagle-import") (part "C-EUC0603"))
    )
    (comp (ref "C13")
      (value "100nF")
      (footprint "eagle-import:C0603")
      (libsource (lib "eagle-import") (part "C-EUC0603"))
    )
    (comp (ref "C14")
      (value "100nF")
      (footprint "eagle-import:C0603")
      (libsource (lib "eagle-import") (part "C-EUC0603"))
    )
    (comp (ref "C15")
      (value "100nF")
      (footprint "eagle-import:C0603")
      (libsource (lib "eagle-import") (part "C-EUC0603"))
    )
    (comp (ref "D00")
      (value "B5819W SL")
      (footprint "eagle-import:SOD-123")
      (libsource (lib "eagle-import") (part "1N5819WS"))
    )
    (comp (ref "D65")
      (value "1N5819WS")
      (footprint "eagle-import:SOD-123")
      (libsource (lib "eagle-import") (part "1N5819WS"))
    )
    (comp (ref "D66")
      (value "1N5819WS")
      (footprint "eagle-import:SOD-123")
      (libsource (lib "eagle-import") (part "1N5819WS"))
    )
    (comp (ref "D67")
      (value "1N5819WS")
      (footprint "eagle-import:SOD-123")
      (libsource (lib "eagle-import") (part "1N5819WS"))
    )
    (comp (ref "D69")
      (value "1N5819WS")
      (footprint "eagle-import:SOD-123")
      (libsource (lib "eagle-import") (part "1N5819WS"))
    )
    (comp (ref "D80")
      (value "BAS70-05")
      (footprint "eagle-import:SOT23")
      (libsource (lib "eagle-import") (part "BAS70-05"))
    )
    (comp (ref "DIP-SW")
      (value "DIP004")
      (footprint "eagle-import:DIP-1.27-004")
      (libsource (lib "eagle-import") (part "DIP004"))
    )
    (comp (ref "ESD")
      (value "ESD_SRV05-4")
      (footprint "eagle-import:SOT-23-6L")
      (libsource (lib "eagle-import") (part "ESD_SRV05-4"))
    )
    (comp (ref "FP_AP2")
      (value "FOOTPRINT-AP2")
      (footprint "eagle-import:FOOTPRINT-AP2")
      (libsource (lib "eagle-import") (part "FOOTPRINT-AP2"))
    )
    (comp (ref "H5")
      (value "STAND-OFF-REFLOW2.5MM_TALL")
      (footprint "eagle-import:STAND-OFF-REFLOW-M2.5")
      (libsource (lib "eagle-import") (part "STAND-OFF-REFLOW2.5MM_TALL"))
    )
    (comp (ref "J-52")
      (value "CONN_03")
      (footprint "eagle-import:1X03")
      (libsource (lib "eagle-import") (part "CONN_03"))
    )
    (comp (ref "J-63")
      (value "CONN_01")
      (footprint "eagle-import:1X01")
      (libsource (lib "eagle-import") (part "CONN_01"))
    )
    (comp (ref "J-BOOT")
      (value "CONN_02")
      (footprint "eagle-import:1X02")
      (libsource (lib "eagle-import") (part "CONN_02"))
    )
    (comp (ref "J-HOST")
      (value "CONN_02")
      (footprint "eagle-import:1X02")
      (libsource (lib "eagle-import") (part "CONN_02"))
    )
    (comp (ref "J-LED")
      (value "CONN_03")
      (footprint "eagle-import:1X03")
      (libsource (lib "eagle-import") (part "CONN_03"))
    )
    (comp (ref "J-TTP")
      (value "SM03B-SRSS-TB")
      (footprint "eagle-import:CONN_SM03B-SRSS-TB_JST")
      (libsource (lib "eagle-import") (part "SM03B-SRSS-TB"))
    )
    (comp (ref "J-UBS")
      (value "USB_C_2-LAYER")
      (footprint "eagle-import:USB-C-16P")
      (libsource (lib "eagle-import") (part "USB_C_2-LAYER"))
    )
    (comp (ref "J-UDB")
      (value "SM04B-SRSS-TB(LF)(SN)")
      (footprint "eagle-import:1X04_1MM_RA")
      (libsource (lib "eagle-import") (part "C3_UNIFIEDJS-1MM"))
    )
    (comp (ref "J-VIN")
      (value "JUMPER-1X2")
      (footprint "eagle-import:SOLDERJUMPER_ARROW_NOPASTE")
      (libsource (lib "eagle-import") (part "JUMPER-1X2"))
    )
    (comp (ref "JP-GND")
      (value "G-OPT")
      (footprint "eagle-import:SOLDERJUMPER_ARROW_NOPASTE")
      (libsource (lib "eagle-import") (part "JUMPER-1X2"))
    )
    (comp (ref "LED-5")
      (value "SK6812-E-REVERSE")
      (footprint "eagle-import:SK6812-E-MILL")
      (libsource (lib "eagle-import") (part "SK6812-E-REVERSE"))
    )
    (comp (ref "LED-6")
      (value "SK6812-E-REVERSE")
      (footprint "eagle-import:SK6812-E-MILL")
      (libsource (lib "eagle-import") (part "SK6812-E-REVERSE"))
    )
    (comp (ref "LED-7")
      (value "SK6812-E-REVERSE")
      (footprint "eagle-import:SK6812-E-MILL")
      (libsource (lib "eagle-import") (part "SK6812-E-REVERSE"))
    )
    (comp (ref "LED-8")
      (value "SK6812-E-REVERSE")
      (footprint "eagle-import:SK6812-E-MILL")
      (libsource (lib "eagle-import") (part "SK6812-E-REVERSE"))
    )
    (comp (ref "LED-CL")
      (value "SK6812-E-REVERSE")
      (footprint "eagle-import:SK6812-E-MILL")
      (libsource (lib "eagle-import") (part "SK6812-E-REVERSE"))
    )
    (comp (ref "LM1117")
      (value "AMS1117-3.3")
      (footprint "eagle-import:SOT223")
      (libsource (lib "eagle-import") (part "V_REG_LM1117SOT223"))
    )
    (comp (ref "LOGO1")
      (value "OSHW-LOGOL")
      (footprint "eagle-import:OSHW-LOGO-L")
      (libsource (lib "eagle-import") (part "OSHW-LOGOL"))
    )
    (comp (ref "M1")
      (value "M25C")
      (footprint "eagle-import:8-SOIC")
      (libsource (lib "eagle-import") (part "M25C"))
    )
    (comp (ref "PTC")
      (value "PTC_ASMD1206-150")
      (footprint "eagle-import:SMD_PTC")
      (libsource (lib "eagle-import") (part "PTC_ASMD1206"))
    )
    (comp (ref "Q7")
      (value "2N7002")
      (footprint "eagle-import:SOT23-3")
      (libsource (lib "eagle-import") (part "2N7002-BSS138"))
    )
    (comp (ref "R1")
      (value "5.1K")
      (footprint "eagle-import:R0603")
      (libsource (lib "eagle-import") (part "R-EU_R0603"))
    )
    (comp (ref "R2")
      (value "5.1K")
      (footprint "eagle-import:R0603")
      (libsource (lib "eagle-import") (part "R-EU_R0603"))
    )
    (comp (ref "R3")
      (value "150K")
      (footprint "eagle-import:R0603")
      (libsource (lib "eagle-import") (part "R-EU_R0603"))
    )
    (comp (ref "R4")
      (value "75K")
      (footprint "eagle-import:R0603")
      (libsource (lib "eagle-import") (part "R-EU_R0603"))
    )
    (comp (ref "R5")
      (value "1000K")
      (footprint "eagle-import:0603")
      (libsource (lib "eagle-import") (part "75KOHM-0603-1/10W-1%"))
    )
    (comp (ref "R6")
      (value "220")
      (footprint "eagle-import:R0603")
      (libsource (lib "eagle-import") (part "R-EU_R0603"))
    )
    (comp (ref "R7")
      (value "470")
      (footprint "eagle-import:R0603")
      (libsource (lib "eagle-import") (part "R-EU_R0603"))
    )
    (comp (ref "R8")
      (value "5.1K")
      (footprint "eagle-import:R0603")
      (libsource (lib "eagle-import") (part "R-EU_R0603"))
    )
    (comp (ref "R9")
      (value "5.1K")
      (footprint "eagle-import:R0603")
      (libsource (lib "eagle-import") (part "R-EU_R0603"))
    )
    (comp (ref "R32")
      (value "10K")
      (footprint "eagle-import:R0603")
      (libsource (lib "eagle-import") (part "R-EU_R0603"))
    )
    (comp (ref "S1")
      (value "MOMENTARY-SWITCH-SPST-1")
      (footprint "eagle-import:SKRKAEE020")
      (libsource (lib "eagle-import") (part "MOMENTARY-SWITCH-SPST-1"))
    )
    (comp (ref "S2")
      (value "MOMENTARY-SWITCH-SPST-1")
      (footprint "eagle-import:SKRKAEE020")
      (libsource (lib "eagle-import") (part "MOMENTARY-SWITCH-SPST-1"))
    )
    (comp (ref "S3")
      (value "BOOT")
      (footprint "eagle-import:TACTILE_SWITCH_SMD_5.2MM")
      (libsource (lib "eagle-import") (part "MOMENTARY-SWITCH-SPST-SMD-5.2-TALL-REDUNDANT"))
    )
    (comp (ref "S4")
      (value "BOOT")
      (footprint "eagle-import:TACTILE_SWITCH_SMD_5.2MM")
      (libsource (lib "eagle-import") (part "MOMENTARY-SWITCH-SPST-SMD-5.2-TALL-REDUNDANT"))
    )
    (comp (ref "TP1")
      (value "TEST-POINT.3SQ")
      (footprint "eagle-import:PAD.03X.03-SQ")
      (libsource (lib "eagle-import") (part "TEST-POINT.3SQ"))
    )
    (comp (ref "TP2")
      (value "TEST-POINT.3SQ")
      (footprint "eagle-import:PAD.03X.03-SQ")
      (libsource (lib "eagle-import") (part "TEST-POINT.3SQ"))
    )
    (comp (ref "TP3")
      (value "TEST-POINT.3SQ")
      (footprint "eagle-import:PAD.03X.03-SQ")
      (libsource (lib "eagle-import") (part "TEST-POINT.3SQ"))
    )
    (comp (ref "TTP223")
      (value "TTP223-BA6")
      (footprint "eagle-import:TTP223B")
      (libsource (lib "eagle-import") (part "TTP223-BA6"))
    )
    (comp (ref "TVS")
      (value "TVS_SMF9.0CA")
      (footprint "eagle-import:SOD123FL-BI")
      (libsource (lib "eagle-import") (part "TVS_SMF9.0CA"))
    )
    (comp (ref "U$3")
      (value "MICROMOD-LOGO")
      (footprint "eagle-import:MICROMOD-LOGO")
      (libsource (lib "eagle-import") (part "MICROMOD-LOGO"))
    )
    (comp (ref "U$5")
      (value "SPARKFUN_LOGO0.2")
      (footprint "eagle-import:SFE_LOGO_NAME_FLAME_.2")
      (libsource (lib "eagle-import") (part "SPARKFUN_LOGO0.2"))
    )
    (comp (ref "U$6")
      (value "QMK_LOGO")
      (footprint "eagle-import:QMK_LOGO")
      (libsource (lib "eagle-import") (part "QMK_LOGO"))
    )
    (comp (ref "U$8")
      (value "TECSMITH-LOGOLONG")
      (footprint "eagle-import:TECSMITH-NAME")
      (libsource (lib "eagle-import") (part "TECSMITH-LOGOLONG"))
    )
    (comp (ref "U$20")
      (value "FIDUCIAL")
      (footprint "eagle-import:FIDUCIAL")
      (libsource (lib "eagle-import") (part "FIDUCIAL"))
    )
    (comp (ref "U$21")
      (value "FIDUCIAL")
      (footprint "eagle-import:FIDUCIAL")
      (libsource (lib "eagle-import") (part "FIDUCIAL"))
    )
    (comp (ref "U$22")
      (value "FIDUCIAL")
      (footprint "eagle-import:FIDUCIAL")
      (libsource (lib "eagle-import") (part "FIDUCIAL"))
    )
    (comp (ref "U$24")
      (value "FOOTPRINT-BAKENEKO60")
      (footprint "eagle-import:FOOTPRINT-BAKENEKO60")
      (libsource (lib "eagle-import") (part "FOOTPRINT-BAKENEKO60"))
    )
    (comp (ref "U$27")
      (value "FOOTPRINT-DIMS-GH60")
      (footprint "eagle-import:FOOTPRINT-DIMS-GH60")
      (libsource (lib "eagle-import") (part "FOOTPRINT-DIMS-GH60"))
    )
    (comp (ref "X1")
      (value "MICROMOD-2222-C")
      (footprint "eagle-import:M.2-CONNECTOR-E")
      (libsource (lib "eagle-import") (part "MICROMOD-2222-C"))
    )
  )
  (nets
    (net (code "1") (name "52") (class "Default")
      (node (ref "J-52") (pin "2") (pinfunction "2_2") (pintype "passive"))
      (node (ref "X1") (pin "52") (pinfunction "AUD_LRCLK_52") (pintype "bidirectional"))
    )
    (net (code "2") (name "63") (class "Default")
      (node (ref "J-63") (pin "1") (pinfunction "1_1") (pintype "passive"))
      (node (ref "X1") (pin "63") (pinfunction "G10/ADC_D+/CAM_VSYNC_63") (pintype "bidirectional"))
    )
    (net (code "3") (name "BOOT") (class "Default")
      (node (ref "D80") (pin "3") (pinfunction "C_3") (pintype "passive"))
      (node (ref "J-BOOT") (pin "1") (pinfunction "1_1") (pintype "passive"))
      (node (ref "R9") (pin "1") (pinfunction "1_1") (pintype "passive"))
      (node (ref "S3") (pin "3") (pinfunction "2_3") (pintype "passive"))
      (node (ref "S3") (pin "4") (pinfunction "2_4") (pintype "passive"))
      (node (ref "S4") (pin "3") (pinfunction "2_3") (pintype "passive"))
      (node (ref "S4") (pin "4") (pinfunction "2_4") (pintype "passive"))
    )
    (net (code "4") (name "D+") (class "Default")
      (node (ref "ESD") (pin "P$1") (pinfunction "P$1_P$1") (pintype "bidirectional"))
      (node (ref "ESD") (pin "P$6") (pinfunction "P$6_P$6") (pintype "bidirectional"))
      (node (ref "J-UBS") (pin "A6") (pinfunction "D+_A6") (pintype "bidirectional"))
      (node (ref "J-UBS") (pin "B6") (pinfunction "D+_B6") (pintype "bidirectional"))
      (node (ref "J-UDB") (pin "3") (pinfunction "D+_3") (pintype "passive"))
      (node (ref "X1") (pin "3") (pinfunction "USB_D+_3") (pintype "bidirectional"))
    )
    (net (code "5") (name "D-") (class "Default")
      (node (ref "ESD") (pin "P$3") (pinfunction "P$3_P$3") (pintype "bidirectional"))
      (node (ref "ESD") (pin "P$4") (pinfunction "P$4_P$4") (pintype "bidirectional"))
      (node (ref "J-UBS") (pin "A7") (pinfunction "D-_A7") (pintype "bidirectional"))
      (node (ref "J-UBS") (pin "B7") (pinfunction "D-_B7") (pintype "bidirectional"))
      (node (ref "J-UDB") (pin "2") (pinfunction "D-_2") (pintype "passive"))
      (node (ref "X1") (pin "5") (pinfunction "USB_D-_5") (pintype "bidirectional"))
    )
    (net (code "6") (name "EE_CS") (class "Default")
      (node (ref "M1") (pin "1") (pinfunction "~{CS}_1") (pintype "bidirectional"))
      (node (ref "X1") (pin "55") (pinfunction "SPI_~{CS}_55") (pintype "bidirectional"))
    )
    (net (code "7") (name "GND") (class "Default")
      (node (ref "74AH") (pin "1") (pinfunction "~{OE}_1") (pintype "input"))
      (node (ref "74AH") (pin "3") (pinfunction "3_GND_3") (pintype "power_in"))
      (node (ref "C01") (pin "2") (pinfunction "2_2") (pintype "passive"))
      (node (ref "C02") (pin "2") (pinfunction "2_2") (pintype "passive"))
      (node (ref "C03") (pin "2") (pinfunction "2_2") (pintype "passive"))
      (node (ref "C04") (pin "2") (pinfunction "2_2") (pintype "passive"))
      (node (ref "C05") (pin "2") (pinfunction "2_2") (pintype "passive"))
      (node (ref "C06") (pin "2") (pinfunction "2_2") (pintype "passive"))
      (node (ref "C07") (pin "2") (pinfunction "2_2") (pintype "passive"))
      (node (ref "C08") (pin "2") (pinfunction "2_2") (pintype "passive"))
      (node (ref "C09") (pin "2") (pinfunction "2_2") (pintype "passive"))
      (node (ref "C10") (pin "2") (pinfunction "2_2") (pintype "passive"))
      (node (ref "C11") (pin "2") (pinfunction "2_2") (pintype "passive"))
      (node (ref "C12") (pin "2") (pinfunction "2_2") (pintype "passive"))
      (node (ref "C13") (pin "2") (pinfunction "2_2") (pintype "passive"))
      (node (ref "C14") (pin "2") (pinfunction "2_2") (pintype "passive"))
      (node (ref "C15") (pin "2") (pinfunction "2_2") (pintype "passive"))
      (node (ref "ESD") (pin "P$2") (pinfunction "P$2_P$2") (pintype "bidirectional"))
      (node (ref "H5") (pin "1") (pinfunction "1_1") (pintype "bidirectional"))
      (node (ref "J-52") (pin "1") (pinfunction "1_1") (pintype "passive"))
      (node (ref "J-BOOT") (pin "2") (pinfunction "2_2") (pintype "passive"))
      (node (ref "J-LED") (pin "1") (pinfunction "1_1") (pintype "passive"))
      (node (ref "J-TTP") (pin "1") (pinfunction "1_1") (pintype "power_in"))
      (node (ref "J-TTP") (pin "4") (pinfunction "M_4") (pintype "bidirectional"))
      (node (ref "J-TTP") (pin "5") (pinfunction "M_5") (pintype "bidirectional"))
      (node (ref "J-UBS") (pin "GND") (pinfunction "GND_GND") (pintype "bidirectional"))
      (node (ref "J-UBS") (pin "GND2") (pinfunction "GND_GND2") (pintype "bidirectional"))
      (node (ref "J-UDB") (pin "4") (pinfunction "GND_4") (pintype "power_in"))
      (node (ref "LED-5") (pin "3-GND") (pinfunction "3_GND_3-GND") (pintype "power_in"))
      (node (ref "LED-6") (pin "3-GND") (pinfunction "3_GND_3-GND") (pintype "power_in"))
      (node (ref "LED-7") (pin "3-GND") (pinfunction "3_GND_3-GND") (pintype "power_in"))
      (node (ref "LED-8") (pin "3-GND") (pinfunction "3_GND_3-GND") (pintype "power_in"))
      (node (ref "LED-CL") (pin "3-GND") (pinfunction "3_GND_3-GND") (pintype "power_in"))
      (node (ref "LM1117") (pin "1") (pinfunction "ADJ_1") (pintype "input"))
      (node (ref "M1") (pin "4") (pinfunction "GND_4") (pintype "bidirectional"))
      (node (ref "R1") (pin "2") (pinfunction "2_2") (pintype "passive"))
      (node (ref "R2") (pin "2") (pinfunction "2_2") (pintype "passive"))
      (node (ref "R32") (pin "2") (pinfunction "2_2") (pintype "passive"))
      (node (ref "R4") (pin "1") (pinfunction "1_1") (pintype "passive"))
      (node (ref "R5") (pin "1") (pinfunction "1_1") (pintype "passive"))
      (node (ref "R8") (pin "1") (pinfunction "1_1") (pintype "passive"))
      (node (ref "S1") (pin "1") (pinfunction "1_1") (pintype "passive"))
      (node (ref "S2") (pin "1") (pinfunction "1_1") (pintype "passive"))
      (node (ref "S3") (pin "1") (pinfunction "1_1") (pintype "passive"))
      (node (ref "S3") (pin "2") (pinfunction "1_2") (pintype "passive"))
      (node (ref "S4") (pin "1") (pinfunction "1_1") (pintype "passive"))
      (node (ref "S4") (pin "2") (pinfunction "1_2") (pintype "passive"))
      (node (ref "TTP223") (pin "2") (pinfunction "P$2_2") (pintype "power_in"))
      (node (ref "TVS") (pin "P$2") (pinfunction "2_P$2") (pintype "passive"))
      (node (ref "X1") (pin "1") (pinfunction "GND_1") (pintype "bidirectional"))
      (node (ref "X1") (pin "33") (pinfunction "GND_33") (pintype "bidirectional"))
      (node (ref "X1") (pin "36") (pinfunction "GND_36") (pintype "bidirectional"))
      (node (ref "X1") (pin "39") (pinfunction "GND_39") (pintype "bidirectional"))
      (node (ref "X1") (pin "45") (pinfunction "GND_45") (pintype "bidirectional"))
      (node (ref "X1") (pin "7") (pinfunction "GND_7") (pintype "bidirectional"))
      (node (ref "X1") (pin "75") (pinfunction "GND_75") (pintype "bidirectional"))
    )
    (net (code "8") (name "GROUND") (class "Default")
      (node (ref "C06") (pin "1") (pinfunction "1_1") (pintype "passive"))
      (node (ref "J-UBS") (pin "SHLD1") (pinfunction "SHLD_SHLD1") (pintype "bidirectional"))
      (node (ref "J-UBS") (pin "SHLD2") (pinfunction "SHLD_SHLD2") (pintype "bidirectional"))
      (node (ref "J-UBS") (pin "SHLD3") (pinfunction "SHLD_SHLD3") (pintype "bidirectional"))
      (node (ref "J-UBS") (pin "SHLD4") (pinfunction "SHLD_SHLD4") (pintype "bidirectional"))
      (node (ref "J-UBS") (pin "SHLD5") (pinfunction "SHLD_SHLD5") (pintype "bidirectional"))
      (node (ref "J-UBS") (pin "SHLD6") (pinfunction "SHLD_SHLD6") (pintype "bidirectional"))
      (node (ref "J-UBS") (pin "SHLD7") (pinfunction "SHLD_SHLD7") (pintype "bidirectional"))
      (node (ref "J-UBS") (pin "SHLD8") (pinfunction "SHLD_SHLD8") (pintype "bidirectional"))
      (node (ref "JP-GND") (pin "2") (pinfunction "2_2") (pintype "passive"))
      (node (ref "R5") (pin "2") (pinfunction "2_2") (pintype "passive"))
    )
    (net (code "9") (name "LED") (class "Default")
      (node (ref "R6") (pin "2") (pinfunction "2_2") (pintype "passive"))
      (node (ref "X1") (pin "32") (pinfunction "PWM0_32") (pintype "bidirectional"))
    )
    (net (code "10") (name "MISO") (class "Default")
      (node (ref "M1") (pin "2") (pinfunction "DO_2") (pintype "bidirectional"))
      (node (ref "X1") (pin "61") (pinfunction "SPI_SDI_61") (pintype "bidirectional"))
    )
    (net (code "11") (name "MOSI") (class "Default")
      (node (ref "M1") (pin "5") (pinfunction "DIO_5") (pintype "bidirectional"))
      (node (ref "X1") (pin "59") (pinfunction "SPI_SDO_59") (pintype "bidirectional"))
    )
    (net (code "12") (name "MX0") (class "Default")
      (node (ref "D01") (pin "C") (pinfunction "C_C") (pintype "passive"))
      (node (ref "D09") (pin "C") (pinfunction "C_C") (pintype "passive"))
      (node (ref "D15") (pin "C") (pinfunction "C_C") (pintype "passive"))
      (node (ref "D23") (pin "C") (pinfunction "C_C") (pintype "passive"))
      (node (ref "D29") (pin "C") (pinfunction "C_C") (pintype "passive"))
      (node (ref "D37") (pin "C") (pinfunction "C_C") (pintype "passive"))
      (node (ref "D42") (pin "C") (pinfunction "C_C") (pintype "passive"))
      (node (ref "D50") (pin "C") (pinfunction "C_C") (pintype "passive"))
      (node (ref "D55") (pin "C") (pinfunction "C_C") (pintype "passive"))
      (node (ref "X1") (pin "47") (pinfunction "PWM1_47") (pintype "bidirectional"))
    )
    (net (code "13") (name "MX1") (class "Default")
      (node (ref "D02") (pin "C") (pinfunction "C_C") (pintype "passive"))
      (node (ref "D10") (pin "C") (pinfunction "C_C") (pintype "passive"))
      (node (ref "D16") (pin "C") (pinfunction "C_C") (pintype "passive"))
      (node (ref "D24") (pin "C") (pinfunction "C_C") (pintype "passive"))
      (node (ref "D30") (pin "C") (pinfunction "C_C") (pintype "passive"))
      (node (ref "D38") (pin "C") (pinfunction "C_C") (pintype "passive"))
      (node (ref "D43") (pin "C") (pinfunction "C_C") (pintype "passive"))
      (node (ref "D51") (pin "C") (pinfunction "C_C") (pintype "passive"))
      (node (ref "D56") (pin "C") (pinfunction "C_C") (pintype "passive"))
      (node (ref "X1") (pin "19") (pinfunction "RX1_19") (pintype "bidirectional"))
    )
    (net (code "14") (name "MX2") (class "Default")
      (node (ref "D03") (pin "C") (pinfunction "C_C") (pintype "passive"))
      (node (ref "D11") (pin "C") (pinfunction "C_C") (pintype "passive"))
      (node (ref "D17") (pin "C") (pinfunction "C_C") (pintype "passive"))
      (node (ref "D25") (pin "C") (pinfunction "C_C") (pintype "passive"))
      (node (ref "D31") (pin "C") (pinfunction "C_C") (pintype "passive"))
      (node (ref "D39") (pin "C") (pinfunction "C_C") (pintype "passive"))
      (node (ref "D44") (pin "C") (pinfunction "C_C") (pintype "passive"))
      (node (ref "D52") (pin "C") (pinfunction "C_C") (pintype "passive"))
      (node (ref "D57") (pin "C") (pinfunction "C_C") (pintype "passive"))
      (node (ref "X1") (pin "17") (pinfunction "TX1_17") (pintype "bidirectional"))
    )
    (net (code "15") (name "MX3") (class "Default")
      (node (ref "D04") (pin "C") (pinfunction "C_C") (pintype "passive"))
      (node (ref "D12") (pin "C") (pinfunction "C_C") (pintype "passive"))
      (node (ref "D18") (pin "C") (pinfunction "C_C") (pintype "passive"))
      (node (ref "D26") (pin "C") (pinfunction "C_C") (pintype "passive"))
      (node (ref "D32") (pin "C") (pinfunction "C_C") (pintype "passive"))
      (node (ref "D40") (pin "C") (pinfunction "C_C") (pintype "passive"))
      (node (ref "D45") (pin "C") (pinfunction "C_C") (pintype "passive"))
      (node (ref "D53") (pin "C") (pinfunction "C_C") (pintype "passive"))
      (node (ref "D58") (pin "C") (pinfunction "C_C") (pintype "passive"))
      (node (ref "X1") (pin "18") (pinfunction "D1/CAM_TRIG_18") (pintype "bidirectional"))
    )
    (net (code "16") (name "MX4") (class "Default")
      (node (ref "D05") (pin "C") (pinfunction "C_C") (pintype "passive"))
      (node (ref "D13") (pin "C") (pinfunction "C_C") (pintype "passive"))
      (node (ref "D19") (pin "C") (pinfunction "C_C") (pintype "passive"))
      (node (ref "D27") (pin "C") (pinfunction "C_C") (pintype "passive"))
      (node (ref "D33") (pin "C") (pinfunction "C_C") (pintype "passive"))
      (node (ref "D46") (pin "C") (pinfunction "C_C") (pintype "passive"))
      (node (ref "D59") (pin "C") (pinfunction "C_C") (pintype "passive"))
      (node (ref "D63") (pin "C") (pinfunction "C_C") (pintype "passive"))
      (node (ref "D64") (pin "C") (pinfunction "C_C") (pintype "passive"))
      (node (ref "X1") (pin "16") (pinfunction "I2C_~{INT}_16") (pintype "bidirectional"))
    )
    (net (code "17") (name "MX5") (class "Default")
      (node (ref "D06") (pin "C") (pinfunction "C_C") (pintype "passive"))
      (node (ref "D20") (pin "C") (pinfunction "C_C") (pintype "passive"))
      (node (ref "D34") (pin "C") (pinfunction "C_C") (pintype "passive"))
      (node (ref "D47") (pin "C") (pinfunction "C_C") (pintype "passive"))
      (node (ref "D54") (pin "C") (pinfunction "C_C") (pintype "passive"))
      (node (ref "D60") (pin "C") (pinfunction "C_C") (pintype "passive"))
      (node (ref "D65") (pin "C") (pinfunction "C_C") (pintype "passive"))
      (node (ref "D66") (pin "C") (pinfunction "C_C") (pintype "passive"))
      (node (ref "D67") (pin "C") (pinfunction "C_C") (pintype "passive"))
      (node (ref "X1") (pin "14") (pinfunction "I2C_SCL_14") (pintype "bidirectional"))
    )
    (net (code "18") (name "MX6") (class "Default")
      (node (ref "D07") (pin "C") (pinfunction "C_C") (pintype "passive"))
      (node (ref "D14") (pin "C") (pinfunction "C_C") (pintype "passive"))
      (node (ref "D21") (pin "C") (pinfunction "C_C") (pintype "passive"))
      (node (ref "D28") (pin "C") (pinfunction "C_C") (pintype "passive"))
      (node (ref "D35") (pin "C") (pinfunction "C_C") (pintype "passive"))
      (node (ref "D41") (pin "C") (pinfunction "C_C") (pintype "passive"))
      (node (ref "D48") (pin "C") (pinfunction "C_C") (pintype "passive"))
      (node (ref "D61") (pin "C") (pinfunction "C_C") (pintype "passive"))
      (node (ref "D69") (pin "C") (pinfunction "C_C") (pintype "passive"))
      (node (ref "X1") (pin "12") (pinfunction "I2C_SDA_12") (pintype "bidirectional"))
    )
    (net (code "19") (name "MX7") (class "Default")
      (node (ref "D08") (pin "C") (pinfunction "C_C") (pintype "passive"))
      (node (ref "D22") (pin "C") (pinfunction "C_C") (pintype "passive"))
      (node (ref "D36") (pin "C") (pinfunction "C_C") (pintype "passive"))
      (node (ref "D49") (pin "C") (pinfunction "C_C") (pintype "passive"))
      (node (ref "D62") (pin "C") (pinfunction "C_C") (pintype "passive"))
      (node (ref "X1") (pin "10") (pinfunction "D0_10") (pintype "bidirectional"))
    )
    (net (code "20") (name "MY0") (class "Default")
      (node (ref "S_1") (pin "2@1") (pinfunction "1_2@1") (pintype "passive"))
      (node (ref "S_1") (pin "2@2") (pinfunction "1_2@2") (pintype "passive"))
      (node (ref "S_2") (pin "2@1") (pinfunction "1_2@1") (pintype "passive"))
      (node (ref "S_2") (pin "2@2") (pinfunction "1_2@2") (pintype "passive"))
      (node (ref "S_3") (pin "2@1") (pinfunction "1_2@1") (pintype "passive"))
      (node (ref "S_3") (pin "2@2") (pinfunction "1_2@2") (pintype "passive"))
      (node (ref "S_4") (pin "2@1") (pinfunction "1_2@1") (pintype "passive"))
      (node (ref "S_4") (pin "2@2") (pinfunction "1_2@2") (pintype "passive"))
      (node (ref "S_5") (pin "2@1") (pinfunction "1_2@1") (pintype "passive"))
      (node (ref "S_5") (pin "2@2") (pinfunction "1_2@2") (pintype "passive"))
      (node (ref "S_6") (pin "2@1") (pinfunction "1_2@1") (pintype "passive"))
      (node (ref "S_6") (pin "2@2") (pinfunction "1_2@2") (pintype "passive"))
      (node (ref "S_7") (pin "2@1") (pinfunction "1_2@1") (pintype "passive"))
      (node (ref "S_7") (pin "2@2") (pinfunction "1_2@2") (pintype "passive"))
      (node (ref "S_ESC") (pin "2@1") (pinfunction "1_2@1") (pintype "passive"))
      (node (ref "S_ESC") (pin "2@2") (pinfunction "1_2@2") (pintype "passive"))
      (node (ref "X1") (pin "56") (pinfunction "AUD_OUT/CAM_MCLK_56") (pintype "bidirectional"))
    )
    (net (code "21") (name "MY1") (class "Default")
      (node (ref "S_E") (pin "2@1") (pinfunction "1_2@1") (pintype "passive"))
      (node (ref "S_E") (pin "2@2") (pinfunction "1_2@2") (pintype "passive"))
      (node (ref "S_Q") (pin "2@1") (pinfunction "1_2@1") (pintype "passive"))
      (node (ref "S_Q") (pin "2@2") (pinfunction "1_2@2") (pintype "passive"))
      (node (ref "S_R") (pin "2@1") (pinfunction "1_2@1") (pintype "passive"))
      (node (ref "S_R") (pin "2@2") (pinfunction "1_2@2") (pintype "passive"))
      (node (ref "S_T") (pin "2@1") (pinfunction "1_2@1") (pintype "passive"))
      (node (ref "S_T") (pin "2@2") (pinfunction "1_2@2") (pintype "passive"))
      (node (ref "S_TAB") (pin "2@1") (pinfunction "1_2@1") (pintype "passive"))
      (node (ref "S_TAB") (pin "2@2") (pinfunction "1_2@2") (pintype "passive"))
      (node (ref "S_U") (pin "2@1") (pinfunction "1_2@1") (pintype "passive"))
      (node (ref "S_U") (pin "2@2") (pinfunction "1_2@2") (pintype "passive"))
      (node (ref "S_W") (pin "2@1") (pinfunction "1_2@1") (pintype "passive"))
      (node (ref "S_W") (pin "2@2") (pinfunction "1_2@2") (pintype "passive"))
      (node (ref "S_Y") (pin "2@1") (pinfunction "1_2@1") (pintype "passive"))
      (node (ref "S_Y") (pin "2@2") (pinfunction "1_2@2") (pintype "passive"))
      (node (ref "X1") (pin "54") (pinfunction "AUD_IN/CAM_PCLK_54") (pintype "bidirectional"))
    )
    (net (code "22") (name "MY2") (class "Default")
      (node (ref "S_A") (pin "2@1") (pinfunction "1_2@1") (pintype "passive"))
      (node (ref "S_A") (pin "2@2") (pinfunction "1_2@2") (pintype "passive"))
      (node (ref "S_CAPS") (pin "2@1") (pinfunction "1_2@1") (pintype "passive"))
      (node (ref "S_CAPS") (pin "2@2") (pinfunction "1_2@2") (pintype "passive"))
      (node (ref "S_CAPS2") (pin "1") (pinfunction "2_1") (pintype "passive"))
      (node (ref "S_D") (pin "2@1") (pinfunction "1_2@1") (pintype "passive"))
      (node (ref "S_D") (pin "2@2") (pinfunction "1_2@2") (pintype "passive"))
      (node (ref "S_F") (pin "2@1") (pinfunction "1_2@1") (pintype "passive"))
      (node (ref "S_F") (pin "2@2") (pinfunction "1_2@2") (pintype "passive"))
      (node (ref "S_G") (pin "2@1") (pinfunction "1_2@1") (pintype "passive"))
      (node (ref "S_G") (pin "2@2") (pinfunction "1_2@2") (pintype "passive"))
      (node (ref "S_H") (pin "2@1") (pinfunction "1_2@1") (pintype "passive"))
      (node (ref "S_H") (pin "2@2") (pinfunction "1_2@2") (pintype "passive"))
      (node (ref "S_J") (pin "2@1") (pinfunction "1_2@1") (pintype "passive"))
      (node (ref "S_J") (pin "2@2") (pinfunction "1_2@2") (pintype "passive"))
      (node (ref "S_S") (pin "2@1") (pinfunction "1_2@1") (pintype "passive"))
      (node (ref "S_S") (pin "2@2") (pinfunction "1_2@2") (pintype "passive"))
      (node (ref "X1") (pin "50") (pinfunction "AUD_BCLK_50") (pintype "bidirectional"))
    )
    (net (code "23") (name "MY3") (class "Default")
      (node (ref "S_B") (pin "2@1") (pinfunction "1_2@1") (pintype "passive"))
      (node (ref "S_B") (pin "2@2") (pinfunction "1_2@2") (pintype "passive"))
      (node (ref "S_C") (pin "2@1") (pinfunction "1_2@1") (pintype "passive"))
      (node (ref "S_C") (pin "2@2") (pinfunction "1_2@2") (pintype "passive"))
      (node (ref "S_LSFT") (pin "2@1") (pinfunction "1_2@1") (pintype "passive"))
      (node (ref "S_LSFT") (pin "2@2") (pinfunction "1_2@2") (pintype "passive"))
      (node (ref "S_LSFT2") (pin "2@1") (pinfunction "1_2@1") (pintype "passive"))
      (node (ref "S_LSFT2") (pin "2@2") (pinfunction "1_2@2") (pintype "passive"))
      (node (ref "S_N") (pin "2@1") (pinfunction "1_2@1") (pintype "passive"))
      (node (ref "S_N") (pin "2@2") (pinfunction "1_2@2") (pintype "passive"))
      (node (ref "S_NUBS") (pin "2@1") (pinfunction "1_2@1") (pintype "passive"))
      (node (ref "S_NUBS") (pin "2@2") (pinfunction "1_2@2") (pintype "passive"))
      (node (ref "S_V") (pin "2@1") (pinfunction "1_2@1") (pintype "passive"))
      (node (ref "S_V") (pin "2@2") (pinfunction "1_2@2") (pintype "passive"))
      (node (ref "S_X") (pin "2@1") (pinfunction "1_2@1") (pintype "passive"))
      (node (ref "S_X") (pin "2@2") (pinfunction "1_2@2") (pintype "passive"))
      (node (ref "S_Z") (pin "2@1") (pinfunction "1_2@1") (pintype "passive"))
      (node (ref "S_Z") (pin "2@2") (pinfunction "1_2@2") (pintype "passive"))
      (node (ref "X1") (pin "46") (pinfunction "G3/BUS3_46") (pintype "bidirectional"))
    )
    (net (code "24") (name "MY4") (class "Default")
      (node (ref "S_APP") (pin "2@1") (pinfunction "1_2@1") (pintype "passive"))
      (node (ref "S_APP") (pin "2@2") (pinfunction "1_2@2") (pintype "passive"))
      (node (ref "S_FN1") (pin "2@1") (pinfunction "1_2@1") (pintype "passive"))
      (node (ref "S_FN1") (pin "2@2") (pinfunction "1_2@2") (pintype "passive"))
      (node (ref "S_LALT") (pin "2@1") (pinfunction "1_2@1") (pintype "passive"))
      (node (ref "S_LALT") (pin "2@2") (pinfunction "1_2@2") (pintype "passive"))
      (node (ref "S_LALT_2") (pin "1@1") (pinfunction "2_1@1") (pintype "passive"))
      (node (ref "S_LALT_2") (pin "1@2") (pinfunction "2_1@2") (pintype "passive"))
      (node (ref "S_LCTL") (pin "2@1") (pinfunction "1_2@1") (pintype "passive"))
      (node (ref "S_LCTL") (pin "2@2") (pinfunction "1_2@2") (pintype "passive"))
      (node (ref "S_LCTL_2") (pin "1@1") (pinfunction "2_1@1") (pintype "passive"))
      (node (ref "S_LCTL_2") (pin "1@2") (pinfunction "2_1@2") (pintype "passive"))
      (node (ref "S_LGUI") (pin "2@1") (pinfunction "1_2@1") (pintype "passive"))
      (node (ref "S_LGUI") (pin "2@2") (pinfunction "1_2@2") (pintype "passive"))
      (node (ref "S_LGUI_2") (pin "1@1") (pinfunction "2_1@1") (pintype "passive"))
      (node (ref "S_LGUI_2") (pin "1@2") (pinfunction "2_1@2") (pintype "passive"))
      (node (ref "S_RALT") (pin "2@1") (pinfunction "1_2@1") (pintype "passive"))
      (node (ref "S_RALT") (pin "2@2") (pinfunction "1_2@2") (pintype "passive"))
      (node (ref "S_RALT_2") (pin "1@1") (pinfunction "2_1@1") (pintype "passive"))
      (node (ref "S_RALT_2") (pin "1@2") (pinfunction "2_1@2") (pintype "passive"))
      (node (ref "S_RCTL") (pin "2@1") (pinfunction "1_2@1") (pintype "passive"))
      (node (ref "S_RCTL") (pin "2@2") (pinfunction "1_2@2") (pintype "passive"))
      (node (ref "S_RCTL_2") (pin "1@1") (pinfunction "2_1@1") (pintype "passive"))
      (node (ref "S_RCTL_2") (pin "1@2") (pinfunction "2_1@2") (pintype "passive"))
      (node (ref "S_RGUI_2") (pin "1@1") (pinfunction "2_1@1") (pintype "passive"))
      (node (ref "S_RGUI_2") (pin "1@2") (pinfunction "2_1@2") (pintype "passive"))
      (node (ref "S_SPC") (pin "2@1") (pinfunction "1_2@1") (pintype "passive"))
      (node (ref "S_SPC") (pin "2@2") (pinfunction "1_2@2") (pintype "passive"))
      (node (ref "S_SPC_2") (pin "1@1") (pinfunction "2_1@1") (pintype "passive"))
      (node (ref "S_SPC_2") (pin "1@2") (pinfunction "2_1@2") (pintype "passive"))
      (node (ref "X1") (pin "44") (pinfunction "G2/BUS2_44") (pintype "bidirectional"))
    )
    (net (code "25") (name "MY5") (class "Default")
      (node (ref "DIP-SW") (pin "8") (pinfunction "8_8") (pintype "passive"))
      (node (ref "S_0") (pin "2@1") (pinfunction "1_2@1") (pintype "passive"))
      (node (ref "S_0") (pin "2@2") (pinfunction "1_2@2") (pintype "passive"))
      (node (ref "S_8") (pin "2@1") (pinfunction "1_2@1") (pintype "passive"))
      (node (ref "S_8") (pin "2@2") (pinfunction "1_2@2") (pintype "passive"))
      (node (ref "S_9") (pin "2@1") (pinfunction "1_2@1") (pintype "passive"))
      (node (ref "S_9") (pin "2@2") (pinfunction "1_2@2") (pintype "passive"))
      (node (ref "S_BSPC") (pin "2@1") (pinfunction "1_2@1") (pintype "passive"))
      (node (ref "S_BSPC") (pin "2@2") (pinfunction "1_2@2") (pintype "passive"))
      (node (ref "S_BSPC2") (pin "2@1") (pinfunction "1_2@1") (pintype "passive"))
      (node (ref "S_BSPC2") (pin "2@2") (pinfunction "1_2@2") (pintype "passive"))
      (node (ref "S_EQL") (pin "2@1") (pinfunction "1_2@1") (pintype "passive"))
      (node (ref "S_EQL") (pin "2@2") (pinfunction "1_2@2") (pintype "passive"))
      (node (ref "S_MINS") (pin "2@1") (pinfunction "1_2@1") (pintype "passive"))
      (node (ref "S_MINS") (pin "2@2") (pinfunction "1_2@2") (pintype "passive"))
      (node (ref "X1") (pin "42") (pinfunction "G1/BUS1_42") (pintype "bidirectional"))
    )
    (net (code "26") (name "MY6") (class "Default")
      (node (ref "DIP-SW") (pin "7") (pinfunction "7_7") (pintype "passive"))
      (node (ref "S_BSLS") (pin "2@1") (pinfunction "1_2@1") (pintype "passive"))
      (node (ref "S_BSLS") (pin "2@2") (pinfunction "1_2@2") (pintype "passive"))
      (node (ref "S_BSLS2") (pin "2@1") (pinfunction "1_2@1") (pintype "passive"))
      (node (ref "S_BSLS2") (pin "2@2") (pinfunction "1_2@2") (pintype "passive"))
      (node (ref "S_I") (pin "2@1") (pinfunction "1_2@1") (pintype "passive"))
      (node (ref "S_I") (pin "2@2") (pinfunction "1_2@2") (pintype "passive"))
      (node (ref "S_LBRC") (pin "2@1") (pinfunction "1_2@1") (pintype "passive"))
      (node (ref "S_LBRC") (pin "2@2") (pinfunction "1_2@2") (pintype "passive"))
      (node (ref "S_O") (pin "2@1") (pinfunction "1_2@1") (pintype "passive"))
      (node (ref "S_O") (pin "2@2") (pinfunction "1_2@2") (pintype "passive"))
      (node (ref "S_P") (pin "2@1") (pinfunction "1_2@1") (pintype "passive"))
      (node (ref "S_P") (pin "2@2") (pinfunction "1_2@2") (pintype "passive"))
      (node (ref "S_RBRC") (pin "2@1") (pinfunction "1_2@1") (pintype "passive"))
      (node (ref "S_RBRC") (pin "2@2") (pinfunction "1_2@2") (pintype "passive"))
      (node (ref "X1") (pin "40") (pinfunction "G0/BUS0_40") (pintype "bidirectional"))
    )
    (net (code "27") (name "MY7") (class "Default")
      (node (ref "DIP-SW") (pin "6") (pinfunction "6_6") (pintype "passive"))
      (node (ref "S_ENT") (pin "2@1") (pinfunction "1_2@1") (pintype "passive"))
      (node (ref "S_ENT") (pin "2@2") (pinfunction "1_2@2") (pintype "passive"))
      (node (ref "S_ENT2") (pin "2@1") (pinfunction "1_2@1") (pintype "passive"))
      (node (ref "S_ENT2") (pin "2@2") (pinfunction "1_2@2") (pintype "passive"))
      (node (ref "S_K") (pin "2@1") (pinfunction "1_2@1") (pintype "passive"))
      (node (ref "S_K") (pin "2@2") (pinfunction "1_2@2") (pintype "passive"))
      (node (ref "S_L") (pin "2@1") (pinfunction "1_2@1") (pintype "passive"))
      (node (ref "S_L") (pin "2@2") (pinfunction "1_2@2") (pintype "passive"))
      (node (ref "S_QUOT") (pin "2@1") (pinfunction "1_2@1") (pintype "passive"))
      (node (ref "S_QUOT") (pin "2@2") (pinfunction "1_2@2") (pintype "passive"))
      (node (ref "S_SCLN") (pin "2@1") (pinfunction "1_2@1") (pintype "passive"))
      (node (ref "S_SCLN") (pin "2@2") (pinfunction "1_2@2") (pintype "passive"))
      (node (ref "S_SPARE") (pin "2@1") (pinfunction "1_2@1") (pintype "passive"))
      (node (ref "S_SPARE") (pin "2@2") (pinfunction "1_2@2") (pintype "passive"))
      (node (ref "X1") (pin "38") (pinfunction "A1_38") (pintype "bidirectional"))
    )
    (net (code "28") (name "MY8") (class "Default")
      (node (ref "Q7") (pin "3") (pinfunction "D_3") (pintype "bidirectional"))
      (node (ref "S_COM") (pin "2@1") (pinfunction "1_2@1") (pintype "passive"))
      (node (ref "S_COM") (pin "2@2") (pinfunction "1_2@2") (pintype "passive"))
      (node (ref "S_DOT") (pin "2@1") (pinfunction "1_2@1") (pintype "passive"))
      (node (ref "S_DOT") (pin "2@2") (pinfunction "1_2@2") (pintype "passive"))
      (node (ref "S_FN") (pin "2@1") (pinfunction "1_2@1") (pintype "passive"))
      (node (ref "S_FN") (pin "2@2") (pinfunction "1_2@2") (pintype "passive"))
      (node (ref "S_M") (pin "2@1") (pinfunction "1_2@1") (pintype "passive"))
      (node (ref "S_M") (pin "2@2") (pinfunction "1_2@2") (pintype "passive"))
      (node (ref "S_RSFT") (pin "2@1") (pinfunction "1_2@1") (pintype "passive"))
      (node (ref "S_RSFT") (pin "2@2") (pinfunction "1_2@2") (pintype "passive"))
      (node (ref "S_RSFT2") (pin "2@1") (pinfunction "1_2@1") (pintype "passive"))
      (node (ref "S_RSFT2") (pin "2@2") (pinfunction "1_2@2") (pintype "passive"))
      (node (ref "S_SLSH") (pin "2@1") (pinfunction "1_2@1") (pintype "passive"))
      (node (ref "S_SLSH") (pin "2@2") (pinfunction "1_2@2") (pintype "passive"))
      (node (ref "X1") (pin "34") (pinfunction "A0_34") (pintype "bidirectional"))
    )
    (net (code "29") (name "Net-(74AH-A_DIN)") (class "Default")
      (node (ref "74AH") (pin "2") (pinfunction "A_DIN_2") (pintype "input"))
      (node (ref "R6") (pin "1") (pinfunction "1_1") (pintype "passive"))
    )
    (net (code "30") (name "Net-(74AH-Y_DOUT)") (class "Default")
      (node (ref "74AH") (pin "4") (pinfunction "Y_DOUT_4") (pintype "output"))
      (node (ref "R7") (pin "2") (pinfunction "2_2") (pintype "passive"))
    )
    (net (code "31") (name "Net-(D01-PadA)") (class "Default")
      (node (ref "D01") (pin "A") (pinfunction "A_A") (pintype "passive"))
      (node (ref "S_ESC") (pin "1@1") (pinfunction "2_1@1") (pintype "passive"))
      (node (ref "S_ESC") (pin "1@2") (pinfunction "2_1@2") (pintype "passive"))
    )
    (net (code "32") (name "Net-(D02-PadA)") (class "Default")
      (node (ref "D02") (pin "A") (pinfunction "A_A") (pintype "passive"))
      (node (ref "S_1") (pin "1@1") (pinfunction "2_1@1") (pintype "passive"))
      (node (ref "S_1") (pin "1@2") (pinfunction "2_1@2") (pintype "passive"))
    )
    (net (code "33") (name "Net-(D03-PadA)") (class "Default")
      (node (ref "D03") (pin "A") (pinfunction "A_A") (pintype "passive"))
      (node (ref "S_2") (pin "1@1") (pinfunction "2_1@1") (pintype "passive"))
      (node (ref "S_2") (pin "1@2") (pinfunction "2_1@2") (pintype "passive"))
    )
    (net (code "34") (name "Net-(D04-PadA)") (class "Default")
      (node (ref "D04") (pin "A") (pinfunction "A_A") (pintype "passive"))
      (node (ref "S_3") (pin "1@1") (pinfunction "2_1@1") (pintype "passive"))
      (node (ref "S_3") (pin "1@2") (pinfunction "2_1@2") (pintype "passive"))
    )
    (net (code "35") (name "Net-(D05-PadA)") (class "Default")
      (node (ref "D05") (pin "A") (pinfunction "A_A") (pintype "passive"))
      (node (ref "S_4") (pin "1@1") (pinfunction "2_1@1") (pintype "passive"))
      (node (ref "S_4") (pin "1@2") (pinfunction "2_1@2") (pintype "passive"))
    )
    (net (code "36") (name "Net-(D06-PadA)") (class "Default")
      (node (ref "D06") (pin "A") (pinfunction "A_A") (pintype "passive"))
      (node (ref "S_5") (pin "1@1") (pinfunction "2_1@1") (pintype "passive"))
      (node (ref "S_5") (pin "1@2") (pinfunction "2_1@2") (pintype "passive"))
    )
    (net (code "37") (name "Net-(D07-PadA)") (class "Default")
      (node (ref "D07") (pin "A") (pinfunction "A_A") (pintype "passive"))
      (node (ref "S_6") (pin "1@1") (pinfunction "2_1@1") (pintype "passive"))
      (node (ref "S_6") (pin "1@2") (pinfunction "2_1@2") (pintype "passive"))
    )
    (net (code "38") (name "Net-(D08-PadA)") (class "Default")
      (node (ref "D08") (pin "A") (pinfunction "A_A") (pintype "passive"))
      (node (ref "S_7") (pin "1@1") (pinfunction "2_1@1") (pintype "passive"))
      (node (ref "S_7") (pin "1@2") (pinfunction "2_1@2") (pintype "passive"))
    )
    (net (code "39") (name "Net-(D09-PadA)") (class "Default")
      (node (ref "D09") (pin "A") (pinfunction "A_A") (pintype "passive"))
      (node (ref "S_8") (pin "1@1") (pinfunction "2_1@1") (pintype "passive"))
      (node (ref "S_8") (pin "1@2") (pinfunction "2_1@2") (pintype "passive"))
    )
    (net (code "40") (name "Net-(D10-PadA)") (class "Default")
      (node (ref "D10") (pin "A") (pinfunction "A_A") (pintype "passive"))
      (node (ref "S_9") (pin "1@1") (pinfunction "2_1@1") (pintype "passive"))
      (node (ref "S_9") (pin "1@2") (pinfunction "2_1@2") (pintype "passive"))
    )
    (net (code "41") (name "Net-(D11-PadA)") (class "Default")
      (node (ref "D11") (pin "A") (pinfunction "A_A") (pintype "passive"))
      (node (ref "S_0") (pin "1@1") (pinfunction "2_1@1") (pintype "passive"))
      (node (ref "S_0") (pin "1@2") (pinfunction "2_1@2") (pintype "passive"))
    )
    (net (code "42") (name "Net-(D12-PadA)") (class "Default")
      (node (ref "D12") (pin "A") (pinfunction "A_A") (pintype "passive"))
      (node (ref "S_MINS") (pin "1@1") (pinfunction "2_1@1") (pintype "passive"))
      (node (ref "S_MINS") (pin "1@2") (pinfunction "2_1@2") (pintype "passive"))
    )
    (net (code "43") (name "Net-(D13-PadA)") (class "Default")
      (node (ref "D13") (pin "A") (pinfunction "A_A") (pintype "passive"))
      (node (ref "S_EQL") (pin "1@1") (pinfunction "2_1@1") (pintype "passive"))
      (node (ref "S_EQL") (pin "1@2") (pinfunction "2_1@2") (pintype "passive"))
    )
    (net (code "44") (name "Net-(D14-PadA)") (class "Default")
      (node (ref "D14") (pin "A") (pinfunction "A_A") (pintype "passive"))
      (node (ref "S_BSPC") (pin "1@1") (pinfunction "2_1@1") (pintype "passive"))
      (node (ref "S_BSPC") (pin "1@2") (pinfunction "2_1@2") (pintype "passive"))
      (node (ref "S_BSPC2") (pin "1@1") (pinfunction "2_1@1") (pintype "passive"))
      (node (ref "S_BSPC2") (pin "1@2") (pinfunction "2_1@2") (pintype "passive"))
    )
    (net (code "45") (name "Net-(D15-PadA)") (class "Default")
      (node (ref "D15") (pin "A") (pinfunction "A_A") (pintype "passive"))
      (node (ref "S_TAB") (pin "1@1") (pinfunction "2_1@1") (pintype "passive"))
      (node (ref "S_TAB") (pin "1@2") (pinfunction "2_1@2") (pintype "passive"))
    )
    (net (code "46") (name "Net-(D16-PadA)") (class "Default")
      (node (ref "D16") (pin "A") (pinfunction "A_A") (pintype "passive"))
      (node (ref "S_Q") (pin "1@1") (pinfunction "2_1@1") (pintype "passive"))
      (node (ref "S_Q") (pin "1@2") (pinfunction "2_1@2") (pintype "passive"))
    )
    (net (code "47") (name "Net-(D17-PadA)") (class "Default")
      (node (ref "D17") (pin "A") (pinfunction "A_A") (pintype "passive"))
      (node (ref "S_W") (pin "1@1") (pinfunction "2_1@1") (pintype "passive"))
      (node (ref "S_W") (pin "1@2") (pinfunction "2_1@2") (pintype "passive"))
    )
    (net (code "48") (name "Net-(D18-PadA)") (class "Default")
      (node (ref "D18") (pin "A") (pinfunction "A_A") (pintype "passive"))
      (node (ref "S_E") (pin "1@1") (pinfunction "2_1@1") (pintype "passive"))
      (node (ref "S_E") (pin "1@2") (pinfunction "2_1@2") (pintype "passive"))
    )
    (net (code "49") (name "Net-(D19-PadA)") (class "Default")
      (node (ref "D19") (pin "A") (pinfunction "A_A") (pintype "passive"))
      (node (ref "S_R") (pin "1@1") (pinfunction "2_1@1") (pintype "passive"))
      (node (ref "S_R") (pin "1@2") (pinfunction "2_1@2") (pintype "passive"))
    )
    (net (code "50") (name "Net-(D20-PadA)") (class "Default")
      (node (ref "D20") (pin "A") (pinfunction "A_A") (pintype "passive"))
      (node (ref "S_T") (pin "1@1") (pinfunction "2_1@1") (pintype "passive"))
      (node (ref "S_T") (pin "1@2") (pinfunction "2_1@2") (pintype "passive"))
    )
    (net (code "51") (name "Net-(D21-PadA)") (class "Default")
      (node (ref "D21") (pin "A") (pinfunction "A_A") (pintype "passive"))
      (node (ref "S_Y") (pin "1@1") (pinfunction "2_1@1") (pintype "passive"))
      (node (ref "S_Y") (pin "1@2") (pinfunction "2_1@2") (pintype "passive"))
    )
    (net (code "52") (name "Net-(D22-PadA)") (class "Default")
      (node (ref "D22") (pin "A") (pinfunction "A_A") (pintype "passive"))
      (node (ref "S_U") (pin "1@1") (pinfunction "2_1@1") (pintype "passive"))
      (node (ref "S_U") (pin "1@2") (pinfunction "2_1@2") (pintype "passive"))
    )
    (net (code "53") (name "Net-(D23-PadA)") (class "Default")
      (node (ref "D23") (pin "A") (pinfunction "A_A") (pintype "passive"))
      (node (ref "S_I") (pin "1@1") (pinfunction "2_1@1") (pintype "passive"))
      (node (ref "S_I") (pin "1@2") (pinfunction "2_1@2") (pintype "passive"))
    )
    (net (code "54") (name "Net-(D24-PadA)") (class "Default")
      (node (ref "D24") (pin "A") (pinfunction "A_A") (pintype "passive"))
      (node (ref "S_O") (pin "1@1") (pinfunction "2_1@1") (pintype "passive"))
      (node (ref "S_O") (pin "1@2") (pinfunction "2_1@2") (pintype "passive"))
    )
    (net (code "55") (name "Net-(D25-PadA)") (class "Default")
      (node (ref "D25") (pin "A") (pinfunction "A_A") (pintype "passive"))
      (node (ref "S_P") (pin "1@1") (pinfunction "2_1@1") (pintype "passive"))
      (node (ref "S_P") (pin "1@2") (pinfunction "2_1@2") (pintype "passive"))
    )
    (net (code "56") (name "Net-(D26-PadA)") (class "Default")
      (node (ref "D26") (pin "A") (pinfunction "A_A") (pintype "passive"))
      (node (ref "S_LBRC") (pin "1@1") (pinfunction "2_1@1") (pintype "passive"))
      (node (ref "S_LBRC") (pin "1@2") (pinfunction "2_1@2") (pintype "passive"))
    )
    (net (code "57") (name "Net-(D27-PadA)") (class "Default")
      (node (ref "D27") (pin "A") (pinfunction "A_A") (pintype "passive"))
      (node (ref "S_RBRC") (pin "1@1") (pinfunction "2_1@1") (pintype "passive"))
      (node (ref "S_RBRC") (pin "1@2") (pinfunction "2_1@2") (pintype "passive"))
    )
    (net (code "58") (name "Net-(D28-PadA)") (class "Default")
      (node (ref "D28") (pin "A") (pinfunction "A_A") (pintype "passive"))
      (node (ref "S_BSLS") (pin "1@1") (pinfunction "2_1@1") (pintype "passive"))
      (node (ref "S_BSLS") (pin "1@2") (pinfunction "2_1@2") (pintype "passive"))
      (node (ref "S_BSLS2") (pin "1@1") (pinfunction "2_1@1") (pintype "passive"))
      (node (ref "S_BSLS2") (pin "1@2") (pinfunction "2_1@2") (pintype "passive"))
    )
    (net (code "59") (name "Net-(D30-PadA)") (class "Default")
      (node (ref "D30") (pin "A") (pinfunction "A_A") (pintype "passive"))
      (node (ref "S_A") (pin "1@1") (pinfunction "2_1@1") (pintype "passive"))
      (node (ref "S_A") (pin "1@2") (pinfunction "2_1@2") (pintype "passive"))
    )
    (net (code "60") (name "Net-(D31-PadA)") (class "Default")
      (node (ref "D31") (pin "A") (pinfunction "A_A") (pintype "passive"))
      (node (ref "S_S") (pin "1@1") (pinfunction "2_1@1") (pintype "passive"))
      (node (ref "S_S") (pin "1@2") (pinfunction "2_1@2") (pintype "passive"))
    )
    (net (code "61") (name "Net-(D32-PadA)") (class "Default")
      (node (ref "D32") (pin "A") (pinfunction "A_A") (pintype "passive"))
      (node (ref "S_D") (pin "1@1") (pinfunction "2_1@1") (pintype "passive"))
      (node (ref "S_D") (pin "1@2") (pinfunction "2_1@2") (pintype "passive"))
    )
    (net (code "62") (name "Net-(D33-PadA)") (class "Default")
      (node (ref "D33") (pin "A") (pinfunction "A_A") (pintype "passive"))
      (node (ref "S_F") (pin "1@1") (pinfunction "2_1@1") (pintype "passive"))
      (node (ref "S_F") (pin "1@2") (pinfunction "2_1@2") (pintype "passive"))
    )
    (net (code "63") (name "Net-(D34-PadA)") (class "Default")
      (node (ref "D34") (pin "A") (pinfunction "A_A") (pintype "passive"))
      (node (ref "S_G") (pin "1@1") (pinfunction "2_1@1") (pintype "passive"))
      (node (ref "S_G") (pin "1@2") (pinfunction "2_1@2") (pintype "passive"))
    )
    (net (code "64") (name "Net-(D35-PadA)") (class "Default")
      (node (ref "D35") (pin "A") (pinfunction "A_A") (pintype "passive"))
      (node (ref "S_H") (pin "1@1") (pinfunction "2_1@1") (pintype "passive"))
      (node (ref "S_H") (pin "1@2") (pinfunction "2_1@2") (pintype "passive"))
    )
    (net (code "65") (name "Net-(D36-PadA)") (class "Default")
      (node (ref "D36") (pin "A") (pinfunction "A_A") (pintype "passive"))
      (node (ref "S_J") (pin "1@1") (pinfunction "2_1@1") (pintype "passive"))
      (node (ref "S_J") (pin "1@2") (pinfunction "2_1@2") (pintype "passive"))
    )
    (net (code "66") (name "Net-(D37-PadA)") (class "Default")
      (node (ref "D37") (pin "A") (pinfunction "A_A") (pintype "passive"))
      (node (ref "S_K") (pin "1@1") (pinfunction "2_1@1") (pintype "passive"))
      (node (ref "S_K") (pin "1@2") (pinfunction "2_1@2") (pintype "passive"))
    )
    (net (code "67") (name "Net-(D38-PadA)") (class "Default")
      (node (ref "D38") (pin "A") (pinfunction "A_A") (pintype "passive"))
      (node (ref "S_L") (pin "1@1") (pinfunction "2_1@1") (pintype "passive"))
      (node (ref "S_L") (pin "1@2") (pinfunction "2_1@2") (pintype "passive"))
    )
    (net (code "68") (name "Net-(D39-PadA)") (class "Default")
      (node (ref "D39") (pin "A") (pinfunction "A_A") (pintype "passive"))
      (node (ref "S_SCLN") (pin "1@1") (pinfunction "2_1@1") (pintype "passive"))
      (node (ref "S_SCLN") (pin "1@2") (pinfunction "2_1@2") (pintype "passive"))
    )
    (net (code "69") (name "Net-(D40-PadA)") (class "Default")
      (node (ref "D40") (pin "A") (pinfunction "A_A") (pintype "passive"))
      (node (ref "S_QUOT") (pin "1@1") (pinfunction "2_1@1") (pintype "passive"))
      (node (ref "S_QUOT") (pin "1@2") (pinfunction "2_1@2") (pintype "passive"))
    )
    (net (code "70") (name "Net-(D41-PadA)") (class "Default")
      (node (ref "D41") (pin "A") (pinfunction "A_A") (pintype "passive"))
      (node (ref "S_ENT") (pin "1@1") (pinfunction "2_1@1") (pintype "passive"))
      (node (ref "S_ENT") (pin "1@2") (pinfunction "2_1@2") (pintype "passive"))
      (node (ref "S_ENT2") (pin "1@1") (pinfunction "2_1@1") (pintype "passive"))
      (node (ref "S_ENT2") (pin "1@2") (pinfunction "2_1@2") (pintype "passive"))
    )
    (net (code "71") (name "Net-(D42-PadA)") (class "Default")
      (node (ref "D42") (pin "A") (pinfunction "A_A") (pintype "passive"))
      (node (ref "S_LSFT") (pin "1@1") (pinfunction "2_1@1") (pintype "passive"))
      (node (ref "S_LSFT") (pin "1@2") (pinfunction "2_1@2") (pintype "passive"))
      (node (ref "S_LSFT2") (pin "1@1") (pinfunction "2_1@1") (pintype "passive"))
      (node (ref "S_LSFT2") (pin "1@2") (pinfunction "2_1@2") (pintype "passive"))
    )
    (net (code "72") (name "Net-(D43-PadA)") (class "Default")
      (node (ref "D43") (pin "A") (pinfunction "A_A") (pintype "passive"))
      (node (ref "S_NUBS") (pin "1@1") (pinfunction "2_1@1") (pintype "passive"))
      (node (ref "S_NUBS") (pin "1@2") (pinfunction "2_1@2") (pintype "passive"))
    )
    (net (code "73") (name "Net-(D44-PadA)") (class "Default")
      (node (ref "D44") (pin "A") (pinfunction "A_A") (pintype "passive"))
      (node (ref "S_Z") (pin "1@1") (pinfunction "2_1@1") (pintype "passive"))
      (node (ref "S_Z") (pin "1@2") (pinfunction "2_1@2") (pintype "passive"))
    )
    (net (code "74") (name "Net-(D45-PadA)") (class "Default")
      (node (ref "D45") (pin "A") (pinfunction "A_A") (pintype "passive"))
      (node (ref "S_X") (pin "1@1") (pinfunction "2_1@1") (pintype "passive"))
      (node (ref "S_X") (pin "1@2") (pinfunction "2_1@2") (pintype "passive"))
    )
    (net (code "75") (name "Net-(D46-PadA)") (class "Default")
      (node (ref "D46") (pin "A") (pinfunction "A_A") (pintype "passive"))
      (node (ref "S_C") (pin "1@1") (pinfunction "2_1@1") (pintype "passive"))
      (node (ref "S_C") (pin "1@2") (pinfunction "2_1@2") (pintype "passive"))
    )
    (net (code "76") (name "Net-(D47-PadA)") (class "Default")
      (node (ref "D47") (pin "A") (pinfunction "A_A") (pintype "passive"))
      (node (ref "S_V") (pin "1@1") (pinfunction "2_1@1") (pintype "passive"))
      (node (ref "S_V") (pin "1@2") (pinfunction "2_1@2") (pintype "passive"))
    )
    (net (code "77") (name "Net-(D48-PadA)") (class "Default")
      (node (ref "D48") (pin "A") (pinfunction "A_A") (pintype "passive"))
      (node (ref "S_B") (pin "1@1") (pinfunction "2_1@1") (pintype "passive"))
      (node (ref "S_B") (pin "1@2") (pinfunction "2_1@2") (pintype "passive"))
    )
    (net (code "78") (name "Net-(D49-PadA)") (class "Default")
      (node (ref "D49") (pin "A") (pinfunction "A_A") (pintype "passive"))
      (node (ref "S_N") (pin "1@1") (pinfunction "2_1@1") (pintype "passive"))
      (node (ref "S_N") (pin "1@2") (pinfunction "2_1@2") (pintype "passive"))
    )
    (net (code "79") (name "Net-(D50-PadA)") (class "Default")
      (node (ref "D50") (pin "A") (pinfunction "A_A") (pintype "passive"))
      (node (ref "S_M") (pin "1@1") (pinfunction "2_1@1") (pintype "passive"))
      (node (ref "S_M") (pin "1@2") (pinfunction "2_1@2") (pintype "passive"))
    )
    (net (code "80") (name "Net-(D51-PadA)") (class "Default")
      (node (ref "D51") (pin "A") (pinfunction "A_A") (pintype "passive"))
      (node (ref "S_COM") (pin "1@1") (pinfunction "2_1@1") (pintype "passive"))
      (node (ref "S_COM") (pin "1@2") (pinfunction "2_1@2") (pintype "passive"))
    )
    (net (code "81") (name "Net-(D52-PadA)") (class "Default")
      (node (ref "D52") (pin "A") (pinfunction "A_A") (pintype "passive"))
      (node (ref "S_DOT") (pin "1@1") (pinfunction "2_1@1") (pintype "passive"))
      (node (ref "S_DOT") (pin "1@2") (pinfunction "2_1@2") (pintype "passive"))
    )
    (net (code "82") (name "Net-(D53-PadA)") (class "Default")
      (node (ref "D53") (pin "A") (pinfunction "A_A") (pintype "passive"))
      (node (ref "S_SLSH") (pin "1@1") (pinfunction "2_1@1") (pintype "passive"))
      (node (ref "S_SLSH") (pin "1@2") (pinfunction "2_1@2") (pintype "passive"))
    )
    (net (code "83") (name "Net-(D54-PadA)") (class "Default")
      (node (ref "D54") (pin "A") (pinfunction "A_A") (pintype "passive"))
      (node (ref "S_RSFT") (pin "1@1") (pinfunction "2_1@1") (pintype "passive"))
      (node (ref "S_RSFT") (pin "1@2") (pinfunction "2_1@2") (pintype "passive"))
      (node (ref "S_RSFT2") (pin "1@1") (pinfunction "2_1@1") (pintype "passive"))
      (node (ref "S_RSFT2") (pin "1@2") (pinfunction "2_1@2") (pintype "passive"))
    )
    (net (code "84") (name "Net-(D55-PadA)") (class "Default")
      (node (ref "D55") (pin "A") (pinfunction "A_A") (pintype "passive"))
      (node (ref "S_LCTL") (pin "1@1") (pinfunction "2_1@1") (pintype "passive"))
      (node (ref "S_LCTL") (pin "1@2") (pinfunction "2_1@2") (pintype "passive"))
      (node (ref "S_LCTL_2") (pin "2@1") (pinfunction "1_2@1") (pintype "passive"))
      (node (ref "S_LCTL_2") (pin "2@2") (pinfunction "1_2@2") (pintype "passive"))
    )
    (net (code "85") (name "Net-(D56-PadA)") (class "Default")
      (node (ref "D56") (pin "A") (pinfunction "A_A") (pintype "passive"))
      (node (ref "S_LGUI") (pin "1@1") (pinfunction "2_1@1") (pintype "passive"))
      (node (ref "S_LGUI") (pin "1@2") (pinfunction "2_1@2") (pintype "passive"))
      (node (ref "S_LGUI_2") (pin "2@1") (pinfunction "1_2@1") (pintype "passive"))
      (node (ref "S_LGUI_2") (pin "2@2") (pinfunction "1_2@2") (pintype "passive"))
    )
    (net (code "86") (name "Net-(D57-PadA)") (class "Default")
      (node (ref "D57") (pin "A") (pinfunction "A_A") (pintype "passive"))
      (node (ref "S_LALT") (pin "1@1") (pinfunction "2_1@1") (pintype "passive"))
      (node (ref "S_LALT") (pin "1@2") (pinfunction "2_1@2") (pintype "passive"))
      (node (ref "S_LALT_2") (pin "2@1") (pinfunction "1_2@1") (pintype "passive"))
      (node (ref "S_LALT_2") (pin "2@2") (pinfunction "1_2@2") (pintype "passive"))
    )
    (net (code "87") (name "Net-(D58-PadA)") (class "Default")
      (node (ref "D58") (pin "A") (pinfunction "A_A") (pintype "passive"))
      (node (ref "S_SPC") (pin "1@1") (pinfunction "2_1@1") (pintype "passive"))
      (node (ref "S_SPC") (pin "1@2") (pinfunction "2_1@2") (pintype "passive"))
      (node (ref "S_SPC_2") (pin "2@1") (pinfunction "1_2@1") (pintype "passive"))
      (node (ref "S_SPC_2") (pin "2@2") (pinfunction "1_2@2") (pintype "passive"))
    )
    (net (code "88") (name "Net-(D59-PadA)") (class "Default")
      (node (ref "D59") (pin "A") (pinfunction "A_A") (pintype "passive"))
      (node (ref "S_FN1") (pin "1@1") (pinfunction "2_1@1") (pintype "passive"))
      (node (ref "S_FN1") (pin "1@2") (pinfunction "2_1@2") (pintype "passive"))
    )
    (net (code "89") (name "Net-(D60-PadA)") (class "Default")
      (node (ref "D60") (pin "A") (pinfunction "A_A") (pintype "passive"))
      (node (ref "S_APP") (pin "1@1") (pinfunction "2_1@1") (pintype "passive"))
      (node (ref "S_APP") (pin "1@2") (pinfunction "2_1@2") (pintype "passive"))
      (node (ref "S_RGUI_2") (pin "2@1") (pinfunction "1_2@1") (pintype "passive"))
      (node (ref "S_RGUI_2") (pin "2@2") (pinfunction "1_2@2") (pintype "passive"))
    )
    (net (code "90") (name "Net-(D61-PadA)") (class "Default")
      (node (ref "D61") (pin "A") (pinfunction "A_A") (pintype "passive"))
      (node (ref "S_RALT") (pin "1@1") (pinfunction "2_1@1") (pintype "passive"))
      (node (ref "S_RALT") (pin "1@2") (pinfunction "2_1@2") (pintype "passive"))
      (node (ref "S_RALT_2") (pin "2@1") (pinfunction "1_2@1") (pintype "passive"))
      (node (ref "S_RALT_2") (pin "2@2") (pinfunction "1_2@2") (pintype "passive"))
    )
    (net (code "91") (name "Net-(D62-PadA)") (class "Default")
      (node (ref "D62") (pin "A") (pinfunction "A_A") (pintype "passive"))
      (node (ref "S_RCTL") (pin "1@1") (pinfunction "2_1@1") (pintype "passive"))
      (node (ref "S_RCTL") (pin "1@2") (pinfunction "2_1@2") (pintype "passive"))
      (node (ref "S_RCTL_2") (pin "2@1") (pinfunction "1_2@1") (pintype "passive"))
      (node (ref "S_RCTL_2") (pin "2@2") (pinfunction "1_2@2") (pintype "passive"))
    )
    (net (code "92") (name "Net-(D63-PadA)") (class "Default")
      (node (ref "D63") (pin "A") (pinfunction "A_A") (pintype "passive"))
      (node (ref "S_FN") (pin "1@1") (pinfunction "2_1@1") (pintype "passive"))
      (node (ref "S_FN") (pin "1@2") (pinfunction "2_1@2") (pintype "passive"))
    )
    (net (code "93") (name "Net-(D64-PadA)") (class "Default")
      (node (ref "D64") (pin "A") (pinfunction "A_A") (pintype "passive"))
      (node (ref "S_SPARE") (pin "1@1") (pinfunction "2_1@1") (pintype "passive"))
      (node (ref "S_SPARE") (pin "1@2") (pinfunction "2_1@2") (pintype "passive"))
    )
    (net (code "94") (name "Net-(D65-PadA)") (class "Default")
      (node (ref "D65") (pin "A") (pinfunction "A_A") (pintype "passive"))
      (node (ref "DIP-SW") (pin "1") (pinfunction "1_1") (pintype "passive"))
    )
    (net (code "95") (name "Net-(D66-PadA)") (class "Default")
      (node (ref "D66") (pin "A") (pinfunction "A_A") (pintype "passive"))
      (node (ref "DIP-SW") (pin "2") (pinfunction "2_2") (pintype "passive"))
    )
    (net (code "96") (name "Net-(D67-PadA)") (class "Default")
      (node (ref "D67") (pin "A") (pinfunction "A_A") (pintype "passive"))
      (node (ref "DIP-SW") (pin "3") (pinfunction "3_3") (pintype "passive"))
    )
    (net (code "97") (name "Net-(DIP-SW-Pad4)") (class "Default")
      (node (ref "DIP-SW") (pin "4") (pinfunction "4_4") (pintype "passive"))
      (node (ref "J-VIN") (pin "2") (pinfunction "2_2") (pintype "passive"))
      (node (ref "R3") (pin "2") (pinfunction "2_2") (pintype "passive"))
    )
    (net (code "98") (name "Net-(J-UBS-CC1)") (class "Default")
      (node (ref "J-UBS") (pin "A5") (pinfunction "CC1_A5") (pintype "bidirectional"))
      (node (ref "R1") (pin "1") (pinfunction "1_1") (pintype "passive"))
    )
    (net (code "99") (name "Net-(J-UBS-CC2)") (class "Default")
      (node (ref "J-UBS") (pin "B5") (pinfunction "CC2_B5") (pintype "bidirectional"))
      (node (ref "R2") (pin "1") (pinfunction "1_1") (pintype "passive"))
    )
    (net (code "100") (name "Net-(LED-5-2_DOUT)") (class "Default")
      (node (ref "LED-5") (pin "2-DOUT") (pinfunction "2_DOUT_2-DOUT") (pintype "output"))
      (node (ref "LED-6") (pin "4-DIN") (pinfunction "4_DIN_4-DIN") (pintype "input"))
    )
    (net (code "101") (name "Net-(LED-5-4_DIN)") (class "Default")
      (node (ref "LED-5") (pin "4-DIN") (pinfunction "4_DIN_4-DIN") (pintype "input"))
      (node (ref "LED-CL") (pin "2-DOUT") (pinfunction "2_DOUT_2-DOUT") (pintype "output"))
    )
    (net (code "102") (name "Net-(LED-6-2_DOUT)") (class "Default")
      (node (ref "LED-6") (pin "2-DOUT") (pinfunction "2_DOUT_2-DOUT") (pintype "output"))
      (node (ref "LED-7") (pin "4-DIN") (pinfunction "4_DIN_4-DIN") (pintype "input"))
    )
    (net (code "103") (name "Net-(LED-7-2_DOUT)") (class "Default")
      (node (ref "LED-7") (pin "2-DOUT") (pinfunction "2_DOUT_2-DOUT") (pintype "output"))
      (node (ref "LED-8") (pin "4-DIN") (pinfunction "4_DIN_4-DIN") (pintype "input"))
    )
    (net (code "104") (name "Net-(LED-8-2_DOUT)") (class "Default")
      (node (ref "J-LED") (pin "2") (pinfunction "2_2") (pintype "passive"))
      (node (ref "LED-8") (pin "2-DOUT") (pinfunction "2_DOUT_2-DOUT") (pintype "output"))
    )
    (net (code "105") (name "Net-(LED-CL-4_DIN)") (class "Default")
      (node (ref "LED-CL") (pin "4-DIN") (pinfunction "4_DIN_4-DIN") (pintype "input"))
      (node (ref "R7") (pin "1") (pinfunction "1_1") (pintype "passive"))
    )
    (net (code "106") (name "Net-(Q7-G)") (class "Default")
      (node (ref "Q7") (pin "1") (pinfunction "G_1") (pintype "bidirectional"))
      (node (ref "R32") (pin "1") (pinfunction "1_1") (pintype "passive"))
      (node (ref "TTP223") (pin "1") (pinfunction "P$1_1") (pintype "output"))
    )
    (net (code "107") (name "Net-(Q7-S)") (class "Default")
      (node (ref "D69") (pin "A") (pinfunction "A_A") (pintype "passive"))
      (node (ref "Q7") (pin "2") (pinfunction "S_2") (pintype "bidirectional"))
    )
    (net (code "108") (name "Net-(S_CAPS2-1)") (class "Default")
      (node (ref "D29") (pin "A") (pinfunction "A_A") (pintype "passive"))
      (node (ref "S_CAPS") (pin "1@1") (pinfunction "2_1@1") (pintype "passive"))
      (node (ref "S_CAPS") (pin "1@2") (pinfunction "2_1@2") (pintype "passive"))
      (node (ref "S_CAPS2") (pin "2") (pinfunction "1_2") (pintype "passive"))
    )
    (net (code "109") (name "Net-(TTP223-P$3)") (class "Default")
      (node (ref "J-TTP") (pin "2") (pinfunction "2_2") (pintype "passive"))
      (node (ref "J-TTP") (pin "3") (pinfunction "3_3") (pintype "passive"))
      (node (ref "TTP223") (pin "3") (pinfunction "P$3_3") (pintype "input"))
    )
    (net (code "110") (name "Net-(TTP223-P$4)") (class "Default")
      (node (ref "TP3") (pin "1") (pinfunction "1_1") (pintype "passive"))
      (node (ref "TTP223") (pin "4") (pinfunction "P$4_4") (pintype "bidirectional"))
    )
    (net (code "111") (name "Net-(TTP223-P$6)") (class "Default")
      (node (ref "TP1") (pin "1") (pinfunction "1_1") (pintype "passive"))
      (node (ref "TTP223") (pin "6") (pinfunction "P$6_6") (pintype "bidirectional"))
    )
    (net (code "112") (name "Net-(X1-USBHOST_D+)") (class "Default")
      (node (ref "J-HOST") (pin "1") (pinfunction "1_1") (pintype "passive"))
      (node (ref "X1") (pin "35") (pinfunction "USBHOST_D+_35") (pintype "bidirectional"))
    )
    (net (code "113") (name "Net-(X1-USBHOST_D-)") (class "Default")
      (node (ref "J-HOST") (pin "2") (pinfunction "2_2") (pintype "passive"))
      (node (ref "X1") (pin "37") (pinfunction "USBHOST_D-_37") (pintype "bidirectional"))
    )
    (net (code "114") (name "SC1") (class "Default")
      (node (ref "JP-GND") (pin "1") (pinfunction "1_1") (pintype "passive"))
    )
    (net (code "115") (name "SCK") (class "Default")
      (node (ref "M1") (pin "6") (pinfunction "CLK_6") (pintype "bidirectional"))
      (node (ref "R8") (pin "2") (pinfunction "2_2") (pintype "passive"))
      (node (ref "X1") (pin "57") (pinfunction "SPI_SCK_57") (pintype "bidirectional"))
    )
    (net (code "116") (name "VBUS") (class "Default")
      (node (ref "ESD") (pin "P$5") (pinfunction "P$5_P$5") (pintype "bidirectional"))
      (node (ref "J-UBS") (pin "VBUS1") (pinfunction "VBUS_VBUS1") (pintype "bidirectional"))
      (node (ref "J-UBS") (pin "VBUS2") (pinfunction "VBUS_VBUS2") (pintype "bidirectional"))
      (node (ref "PTC") (pin "P$1") (pinfunction "1_P$1") (pintype "passive"))
    )
    (net (code "117") (name "VCC") (class "Default")
      (node (ref "C01") (pin "1") (pinfunction "1_1") (pintype "passive"))
      (node (ref "C02") (pin "1") (pinfunction "1_1") (pintype "passive"))
      (node (ref "C03") (pin "1") (pinfunction "1_1") (pintype "passive"))
      (node (ref "C13") (pin "1") (pinfunction "1_1") (pintype "passive"))
      (node (ref "C15") (pin "1") (pinfunction "1_1") (pintype "passive"))
      (node (ref "D00") (pin "A") (pinfunction "A_A") (pintype "passive"))
      (node (ref "J-52") (pin "3") (pinfunction "3_3") (pintype "passive"))
      (node (ref "LM1117") (pin "2") (pinfunction "OUT_2") (pintype "output"))
      (node (ref "M1") (pin "3") (pinfunction "~{WP}_3") (pintype "bidirectional"))
      (node (ref "M1") (pin "7") (pinfunction "~{HLD}_7") (pintype "bidirectional"))
      (node (ref "M1") (pin "8") (pinfunction "VCC_8") (pintype "bidirectional"))
      (node (ref "R9") (pin "2") (pinfunction "2_2") (pintype "passive"))
      (node (ref "TP2") (pin "1") (pinfunction "1_1") (pintype "passive"))
      (node (ref "TTP223") (pin "5") (pinfunction "P$5_5") (pintype "power_in"))
      (node (ref "X1") (pin "2") (pinfunction "3.3V_2") (pintype "bidirectional"))
      (node (ref "X1") (pin "4") (pinfunction "3.3V_EN_4") (pintype "bidirectional"))
      (node (ref "X1") (pin "74") (pinfunction "3.3V_74") (pintype "bidirectional"))
    )
    (net (code "118") (name "VIN{slash}3") (class "Default")
      (node (ref "R3") (pin "1") (pinfunction "1_1") (pintype "passive"))
      (node (ref "R4") (pin "2") (pinfunction "2_2") (pintype "passive"))
      (node (ref "X1") (pin "49") (pinfunction "BATT_VIN/3_49") (pintype "bidirectional"))
    )
    (net (code "119") (name "VSUP") (class "Default")
      (node (ref "74AH") (pin "6") (pinfunction "5_VCC_6") (pintype "power_in"))
      (node (ref "C04") (pin "1") (pinfunction "1_1") (pintype "passive"))
      (node (ref "C05") (pin "1") (pinfunction "1_1") (pintype "passive"))
      (node (ref "C07") (pin "1") (pinfunction "1_1") (pintype "passive"))
      (node (ref "C08") (pin "1") (pinfunction "1_1") (pintype "passive"))
      (node (ref "C09") (pin "1") (pinfunction "1_1") (pintype "passive"))
      (node (ref "C10") (pin "1") (pinfunction "1_1") (pintype "passive"))
      (node (ref "C11") (pin "1") (pinfunction "1_1") (pintype "passive"))
      (node (ref "C12") (pin "1") (pinfunction "1_1") (pintype "passive"))
      (node (ref "D00") (pin "C") (pinfunction "C_C") (pintype "passive"))
      (node (ref "DIP-SW") (pin "5") (pinfunction "5_5") (pintype "passive"))
      (node (ref "J-LED") (pin "3") (pinfunction "3_3") (pintype "passive"))
      (node (ref "J-UDB") (pin "1") (pinfunction "VCC_1") (pintype "power_in"))
      (node (ref "J-VIN") (pin "1") (pinfunction "1_1") (pintype "passive"))
      (node (ref "LED-5") (pin "1-VDD") (pinfunction "1_VDD_1-VDD") (pintype "power_in"))
      (node (ref "LED-6") (pin "1-VDD") (pinfunction "1_VDD_1-VDD") (pintype "power_in"))
      (node (ref "LED-7") (pin "1-VDD") (pinfunction "1_VDD_1-VDD") (pintype "power_in"))
      (node (ref "LED-8") (pin "1-VDD") (pinfunction "1_VDD_1-VDD") (pintype "power_in"))
      (node (ref "LED-CL") (pin "1-VDD") (pinfunction "1_VDD_1-VDD") (pintype "power_in"))
      (node (ref "LM1117") (pin "3") (pinfunction "IN_3") (pintype "input"))
      (node (ref "PTC") (pin "P$2") (pinfunction "2_P$2") (pintype "passive"))
      (node (ref "TVS") (pin "P$1") (pinfunction "1_P$1") (pintype "passive"))
      (node (ref "X1") (pin "9") (pinfunction "USB_VIN_9") (pintype "bidirectional"))
    )
    (net (code "120") (name "unconnected-(LM1117-OUT-Pad4)") (class "Default")
      (node (ref "LM1117") (pin "4") (pinfunction "OUT_4") (pintype "output"))
    )
    (net (code "121") (name "unconnected-(X1-AUD_MCLK-Pad58)") (class "Default")
      (node (ref "X1") (pin "58") (pinfunction "AUD_MCLK_58") (pintype "bidirectional"))
    )
    (net (code "122") (name "unconnected-(X1-CAN-RX-Pad41)") (class "Default")
      (node (ref "X1") (pin "41") (pinfunction "CAN-RX_41") (pintype "bidirectional"))
    )
    (net (code "123") (name "unconnected-(X1-CAN-TX-Pad43)") (class "Default")
      (node (ref "X1") (pin "43") (pinfunction "CAN-TX_43") (pintype "bidirectional"))
    )
    (net (code "124") (name "unconnected-(X1-CTS1-Pad15)") (class "Default")
      (node (ref "X1") (pin "15") (pinfunction "CTS1_15") (pintype "bidirectional"))
    )
    (net (code "125") (name "unconnected-(X1-G4{slash}BUS4-Pad48)") (class "Default")
      (node (ref "X1") (pin "48") (pinfunction "G4/BUS4_48") (pintype "bidirectional"))
    )
    (net (code "126") (name "unconnected-(X1-G5{slash}BUS5-Pad73)") (class "Default")
      (node (ref "X1") (pin "73") (pinfunction "G5/BUS5_73") (pintype "bidirectional"))
    )
    (net (code "127") (name "unconnected-(X1-G6{slash}BUS6-Pad71)") (class "Default")
      (node (ref "X1") (pin "71") (pinfunction "G6/BUS6_71") (pintype "bidirectional"))
    )
    (net (code "128") (name "unconnected-(X1-G7{slash}BUS7-Pad69)") (class "Default")
      (node (ref "X1") (pin "69") (pinfunction "G7/BUS7_69") (pintype "bidirectional"))
    )
    (net (code "129") (name "unconnected-(X1-G8-Pad67)") (class "Default")
      (node (ref "X1") (pin "67") (pinfunction "G8_67") (pintype "bidirectional"))
    )
    (net (code "130") (name "unconnected-(X1-G9{slash}ADC_D-{slash}CAM_HSYNC-Pad65)") (class "Default")
      (node (ref "X1") (pin "65") (pinfunction "G9/ADC_D-/CAM_HSYNC_65") (pintype "bidirectional"))
    )
    (net (code "131") (name "unconnected-(X1-G11-Pad8)") (class "Default")
      (node (ref "X1") (pin "8") (pinfunction "G11_8") (pintype "bidirectional"))
    )
    (net (code "132") (name "unconnected-(X1-I2C_SCL1-Pad53)") (class "Default")
      (node (ref "X1") (pin "53") (pinfunction "I2C_SCL1_53") (pintype "bidirectional"))
    )
    (net (code "133") (name "unconnected-(X1-I2C_SDA1-Pad51)") (class "Default")
      (node (ref "X1") (pin "51") (pinfunction "I2C_SDA1_51") (pintype "bidirectional"))
    )
    (net (code "134") (name "unconnected-(X1-RTC_3V-Pad72)") (class "Default")
      (node (ref "X1") (pin "72") (pinfunction "RTC_3V_72") (pintype "bidirectional"))
    )
    (net (code "135") (name "unconnected-(X1-RTS1-Pad13)") (class "Default")
      (node (ref "X1") (pin "13") (pinfunction "RTS1_13") (pintype "bidirectional"))
    )
    (net (code "136") (name "unconnected-(X1-RX2-Pad20)") (class "Default")
      (node (ref "X1") (pin "20") (pinfunction "RX2_20") (pintype "bidirectional"))
    )
    (net (code "137") (name "unconnected-(X1-SDIO_DATA1-Pad66)") (class "Default")
      (node (ref "X1") (pin "66") (pinfunction "SDIO_DATA1_66") (pintype "bidirectional"))
    )
    (net (code "138") (name "unconnected-(X1-SDIO_DATA2-Pad68)") (class "Default")
      (node (ref "X1") (pin "68") (pinfunction "SDIO_DATA2_68") (pintype "bidirectional"))
    )
    (net (code "139") (name "unconnected-(X1-SPI_SCK1{slash}SDIO_CLK-Pad60)") (class "Default")
      (node (ref "X1") (pin "60") (pinfunction "SPI_SCK1/SDIO_CLK_60") (pintype "bidirectional"))
    )
    (net (code "140") (name "unconnected-(X1-SPI_SDI1{slash}SDIO_DATA0-Pad64)") (class "Default")
      (node (ref "X1") (pin "64") (pinfunction "SPI_SDI1/SDIO_DATA0_64") (pintype "bidirectional"))
    )
    (net (code "141") (name "unconnected-(X1-SPI_SDO1{slash}SDIO_CMD-Pad62)") (class "Default")
      (node (ref "X1") (pin "62") (pinfunction "SPI_SDO1/SDIO_CMD_62") (pintype "bidirectional"))
    )
    (net (code "142") (name "unconnected-(X1-SPI_~{CS1}{slash}SDIO_DATA3-Pad70)") (class "Default")
      (node (ref "X1") (pin "70") (pinfunction "SPI_~{CS1}/SDIO_DATA3_70") (pintype "bidirectional"))
    )
    (net (code "143") (name "unconnected-(X1-SWDCK-Pad21)") (class "Default")
      (node (ref "X1") (pin "21") (pinfunction "SWDCK_21") (pintype "bidirectional"))
    )
    (net (code "144") (name "unconnected-(X1-SWDIO-Pad23)") (class "Default")
      (node (ref "X1") (pin "23") (pinfunction "SWDIO_23") (pintype "bidirectional"))
    )
    (net (code "145") (name "unconnected-(X1-TX2-Pad22)") (class "Default")
      (node (ref "X1") (pin "22") (pinfunction "TX2_22") (pintype "bidirectional"))
    )
    (net (code "146") (name "~{BOOT}") (class "Default")
      (node (ref "C14") (pin "1") (pinfunction "1_1") (pintype "passive"))
      (node (ref "D80") (pin "1") (pinfunction "A1_1") (pintype "passive"))
      (node (ref "S2") (pin "2") (pinfunction "3_2") (pintype "passive"))
      (node (ref "X1") (pin "11") (pinfunction "~{BOOT}_11") (pintype "bidirectional"))
    )
    (net (code "147") (name "~{RESET}") (class "Default")
      (node (ref "D80") (pin "2") (pinfunction "A2_2") (pintype "passive"))
      (node (ref "S1") (pin "2") (pinfunction "3_2") (pintype "passive"))
      (node (ref "X1") (pin "6") (pinfunction "~{RESET}_6") (pintype "bidirectional"))
    )
  )
)
